# usb_hub_test.net
KiCad netlist of a schematic drawn in EAGLE
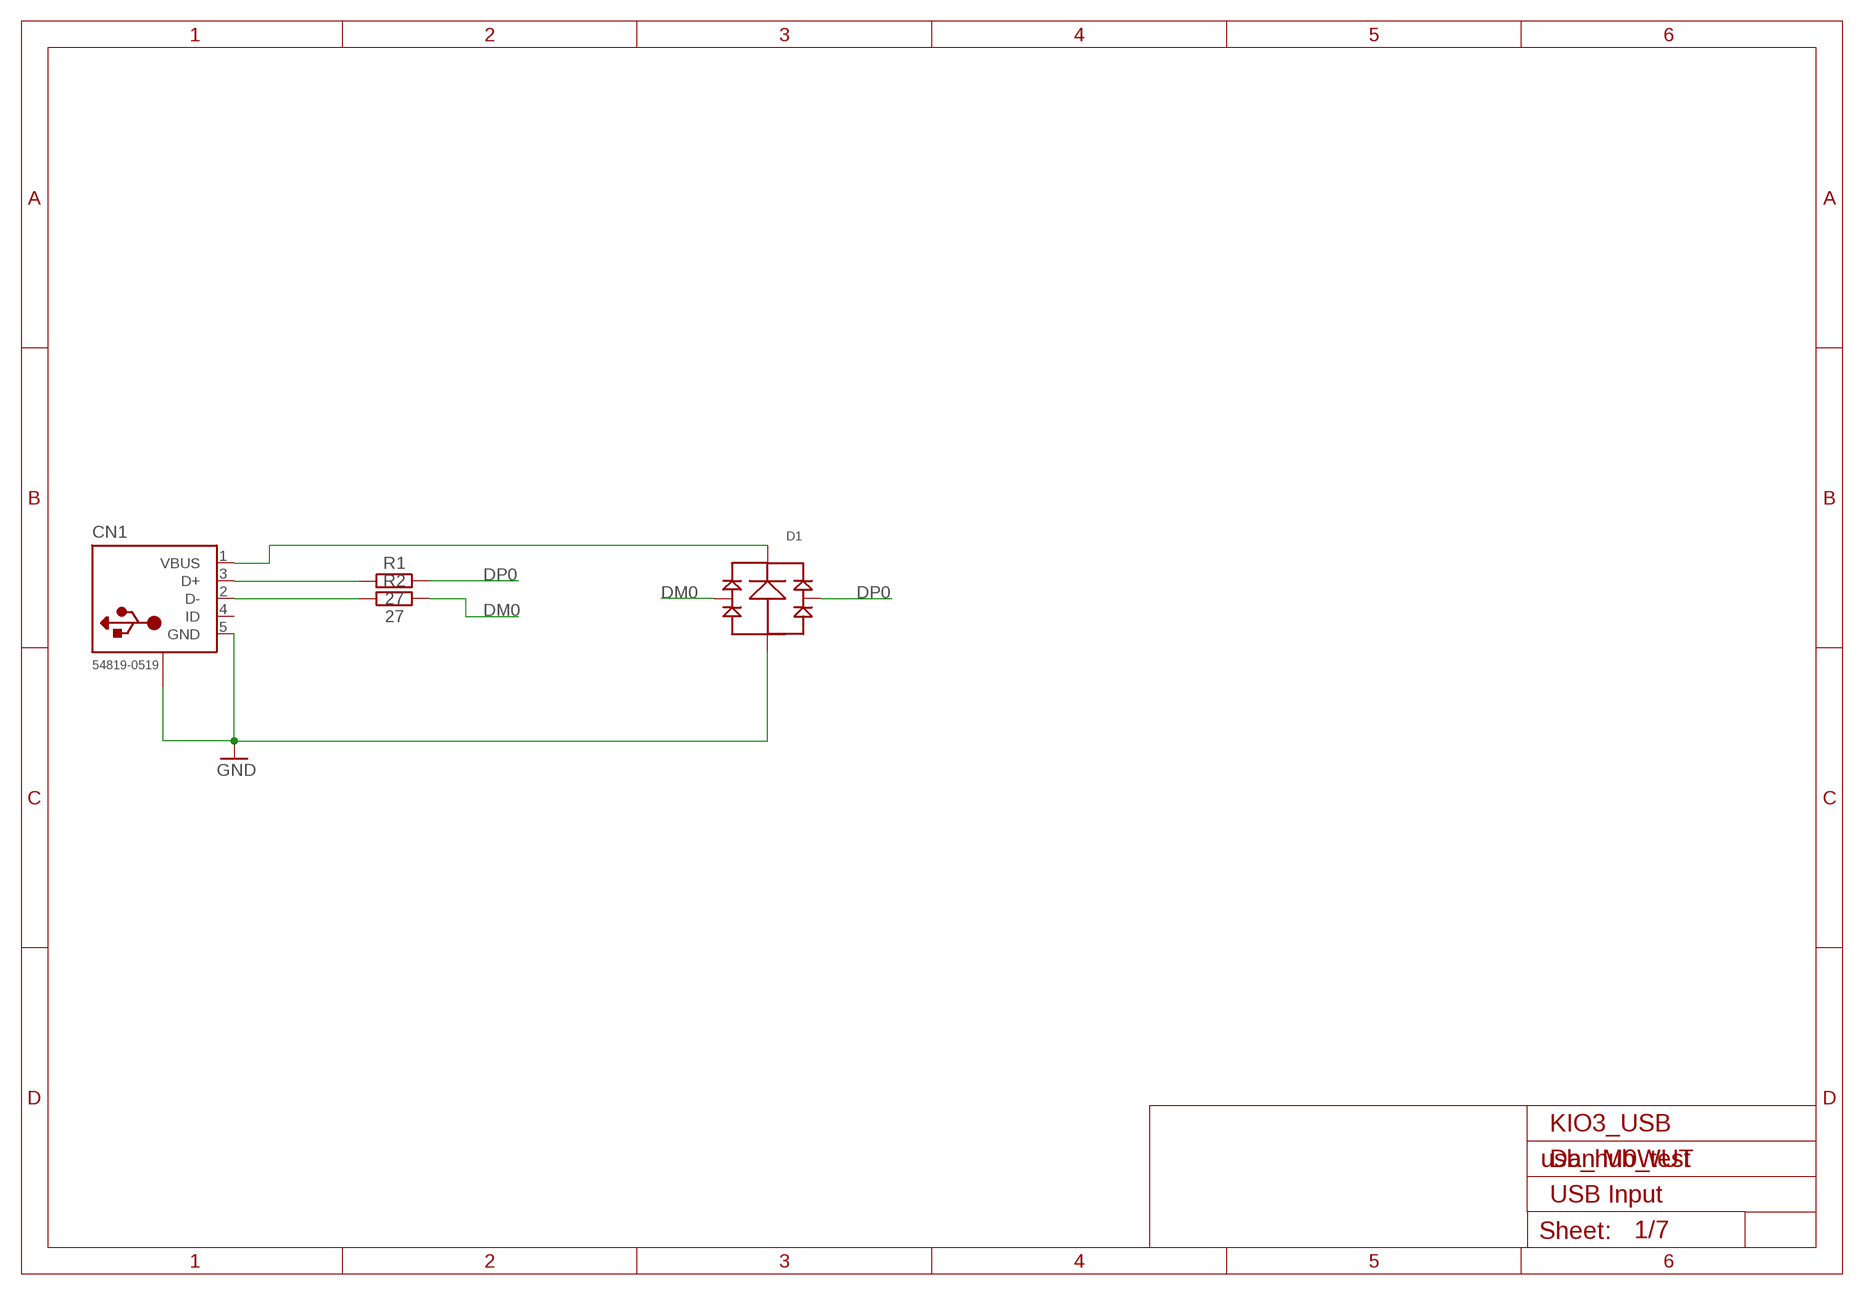
[diagram p0: schematic, sheet 1]
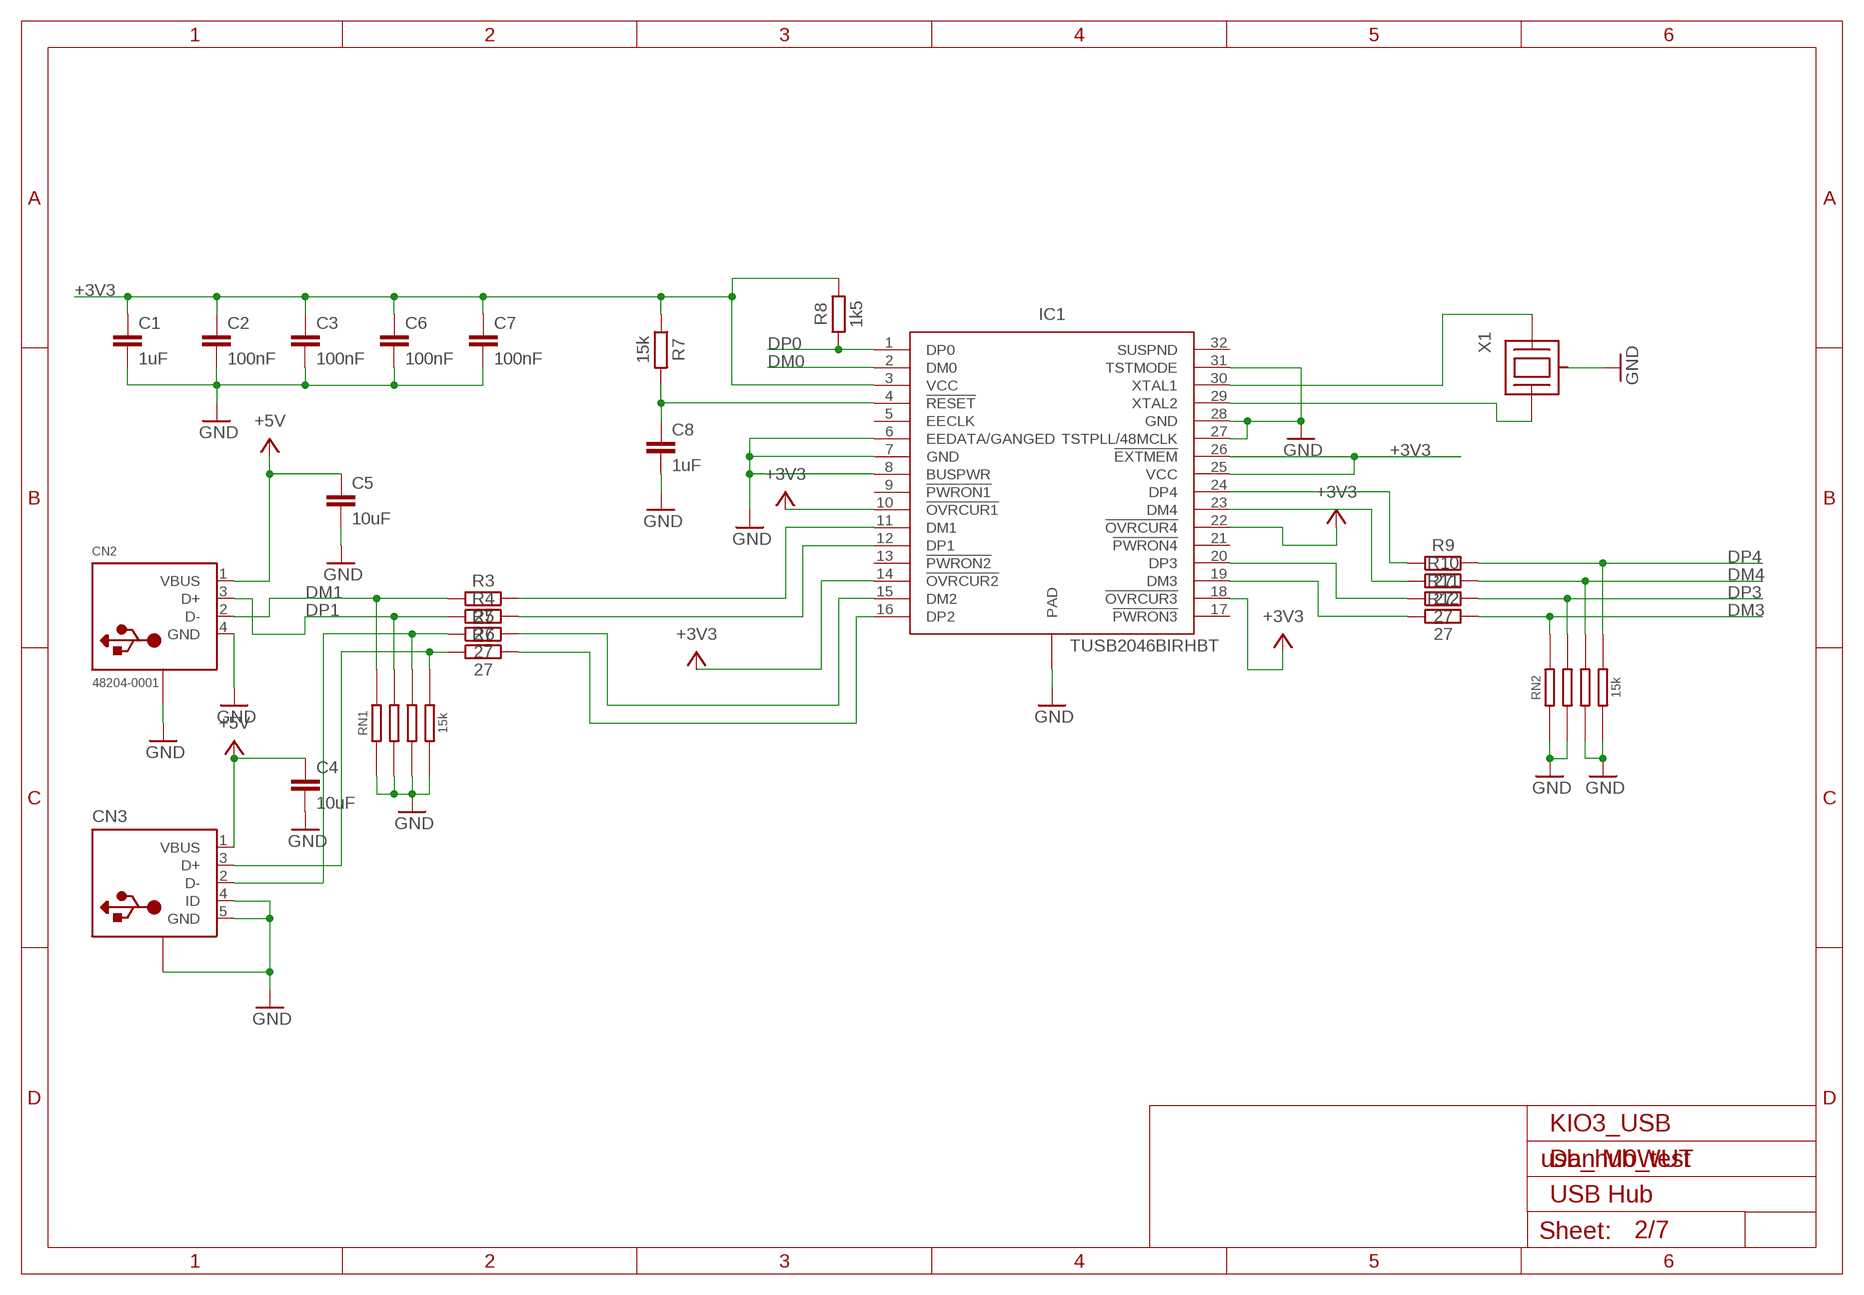
[diagram p1: schematic, sheet 2]
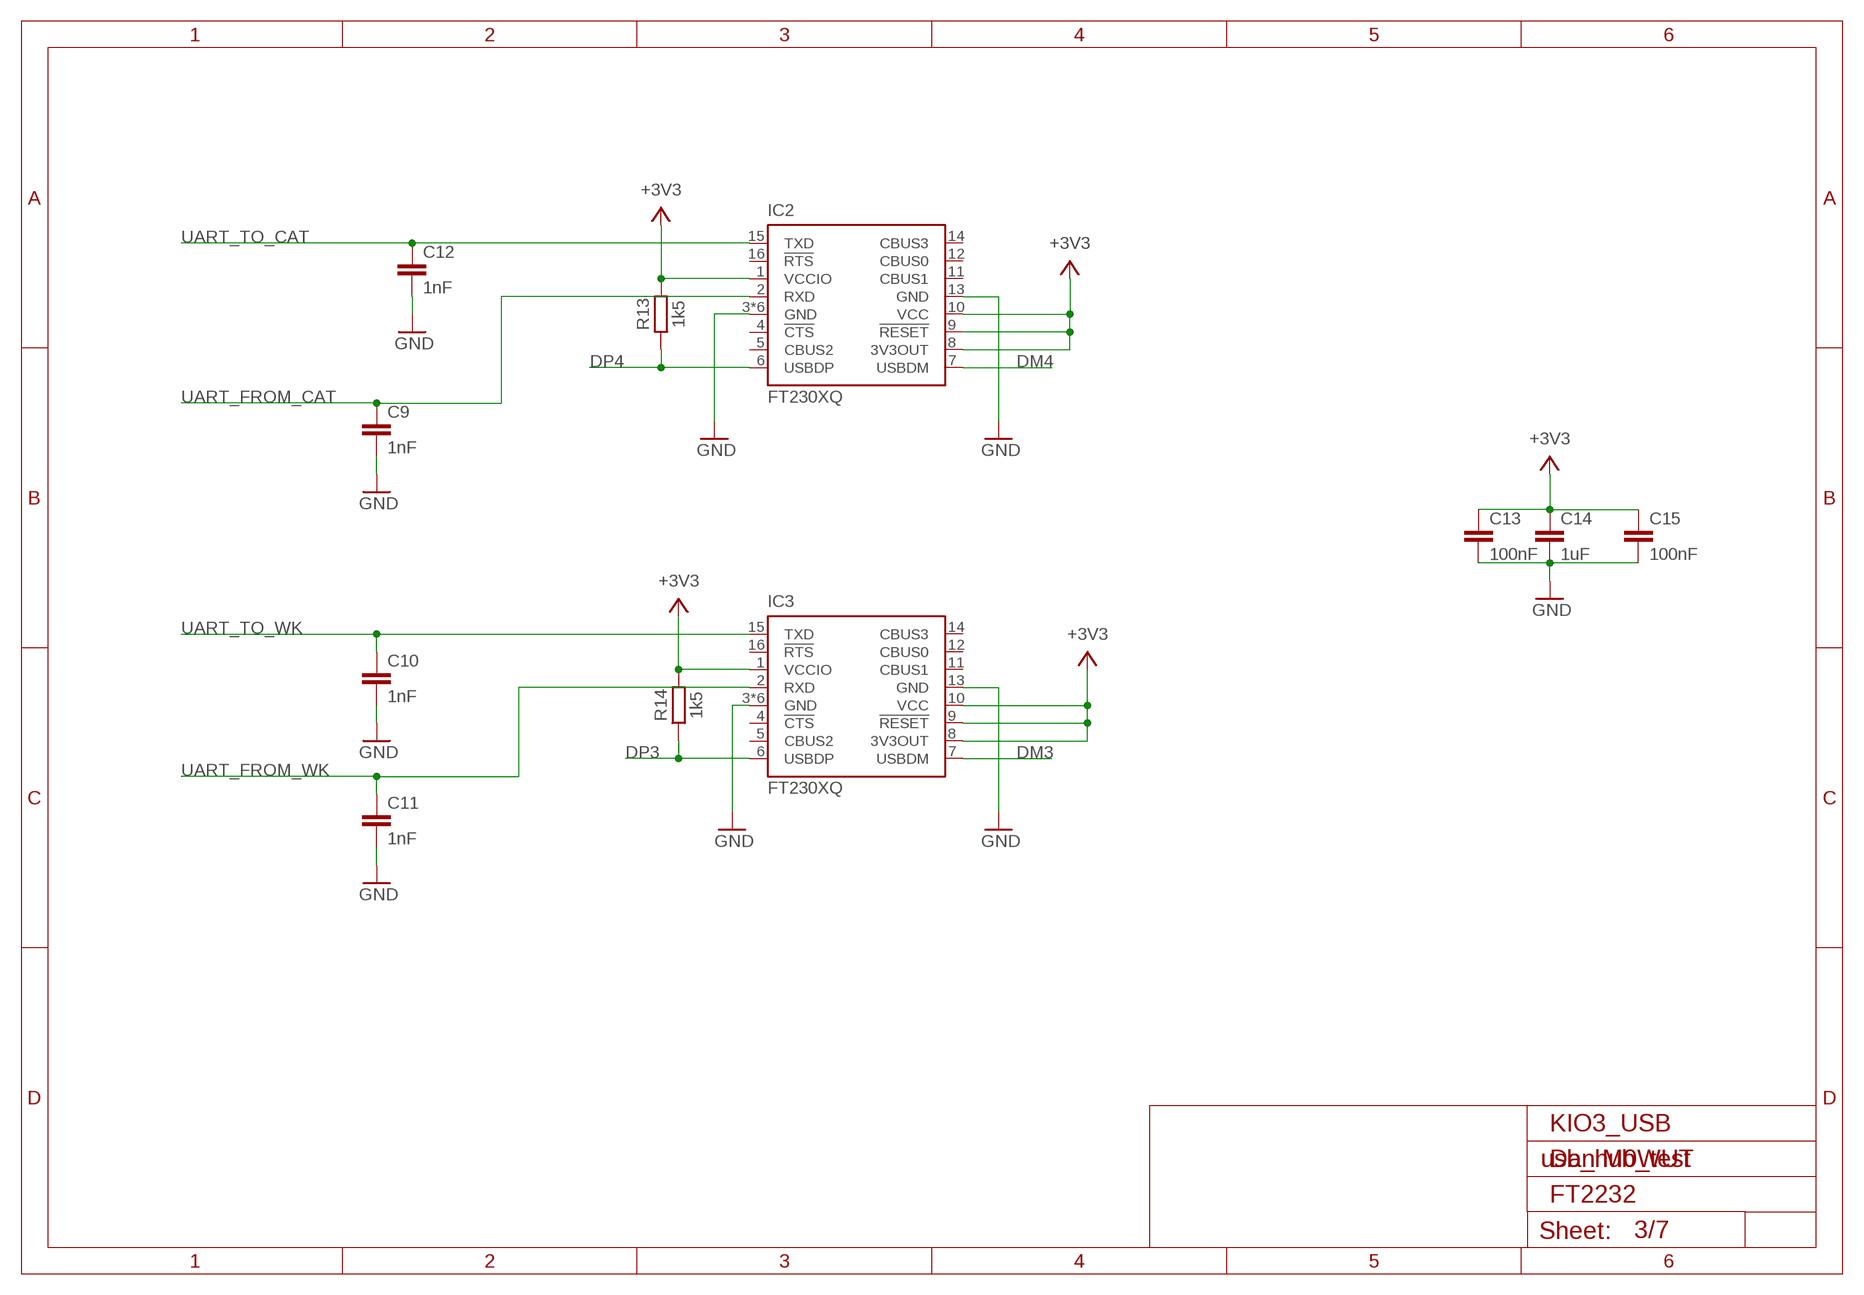
[diagram p2: schematic, sheet 3]
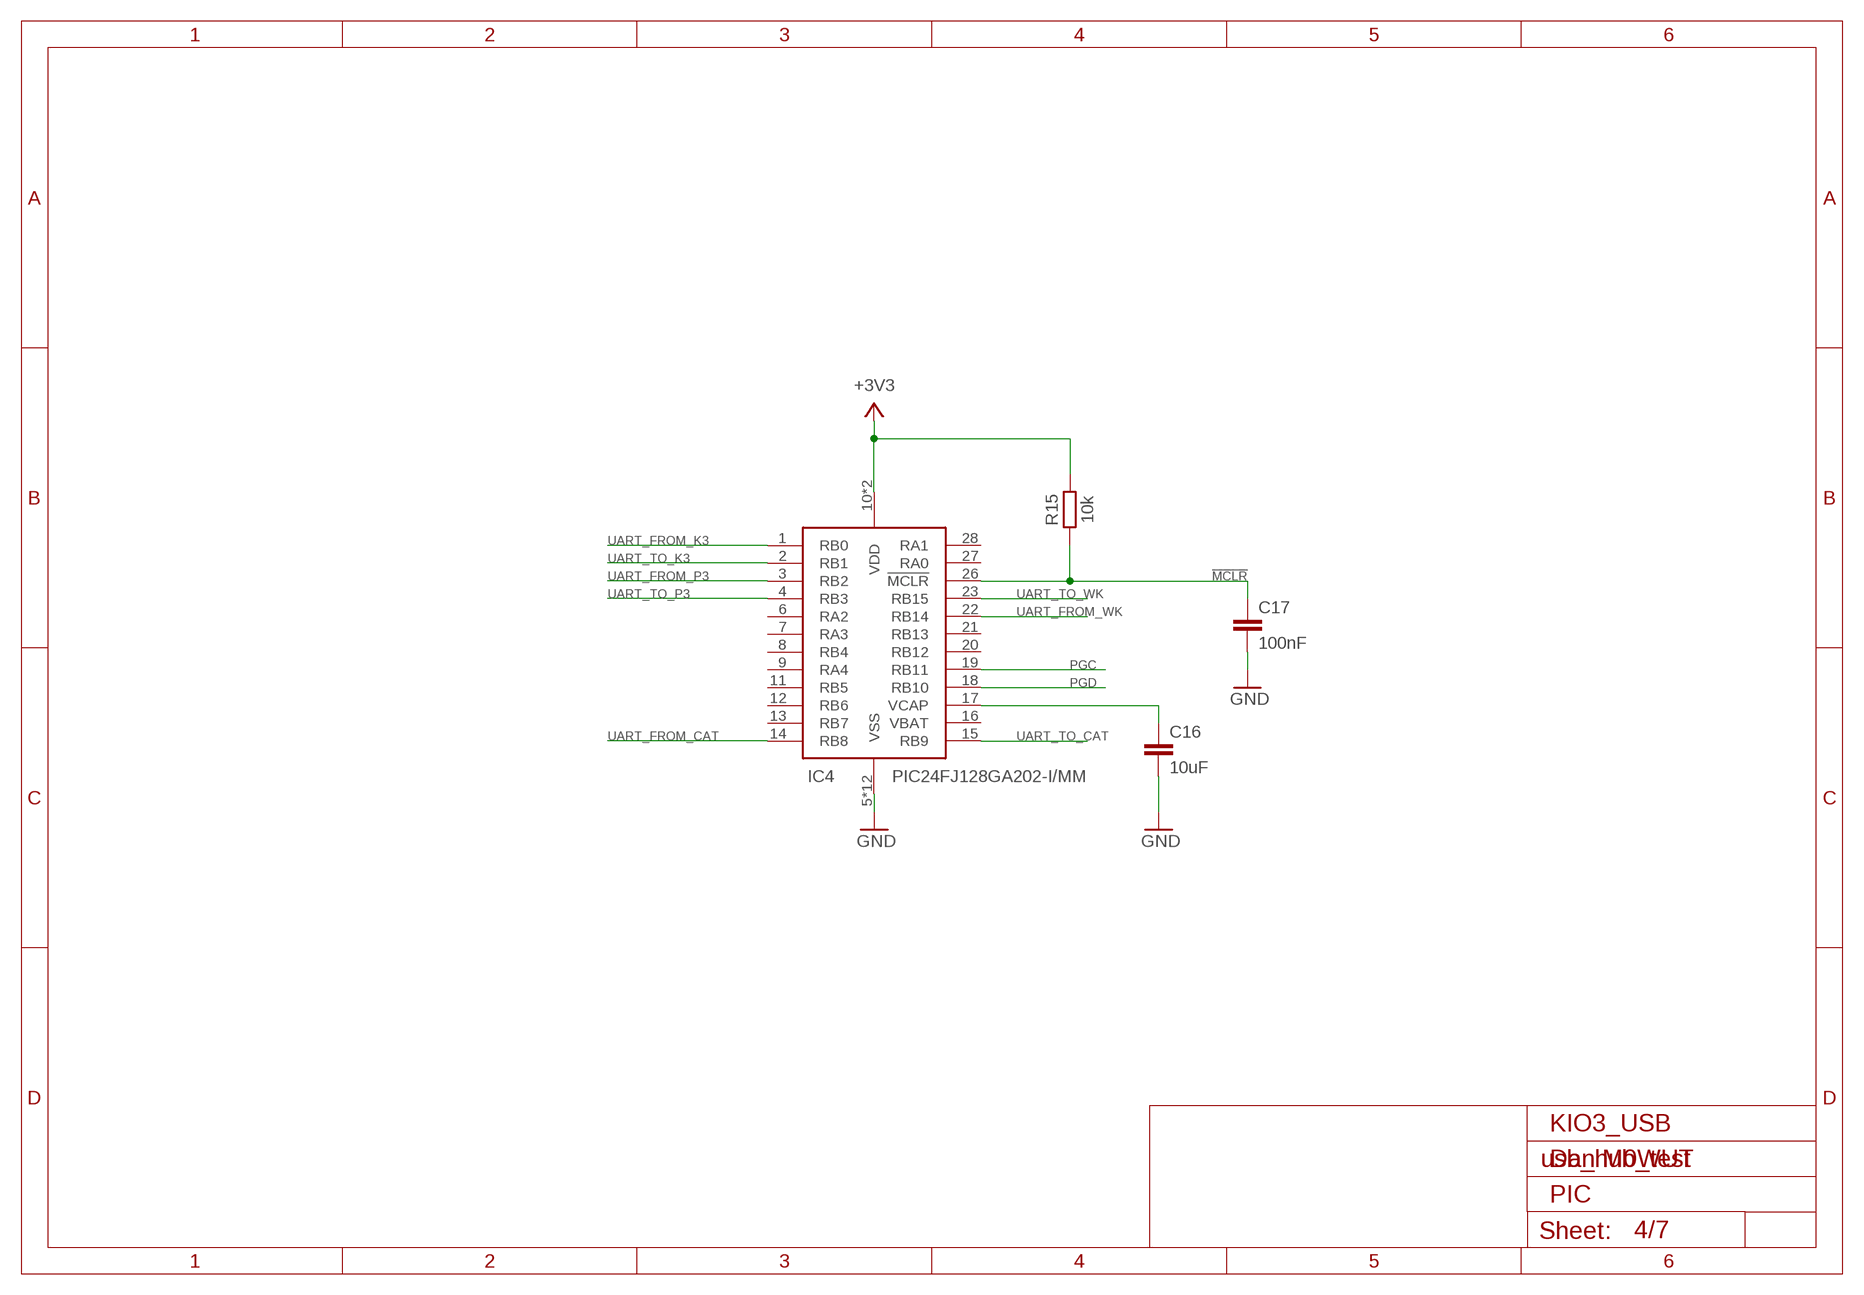
[diagram p3: schematic, sheet 4]
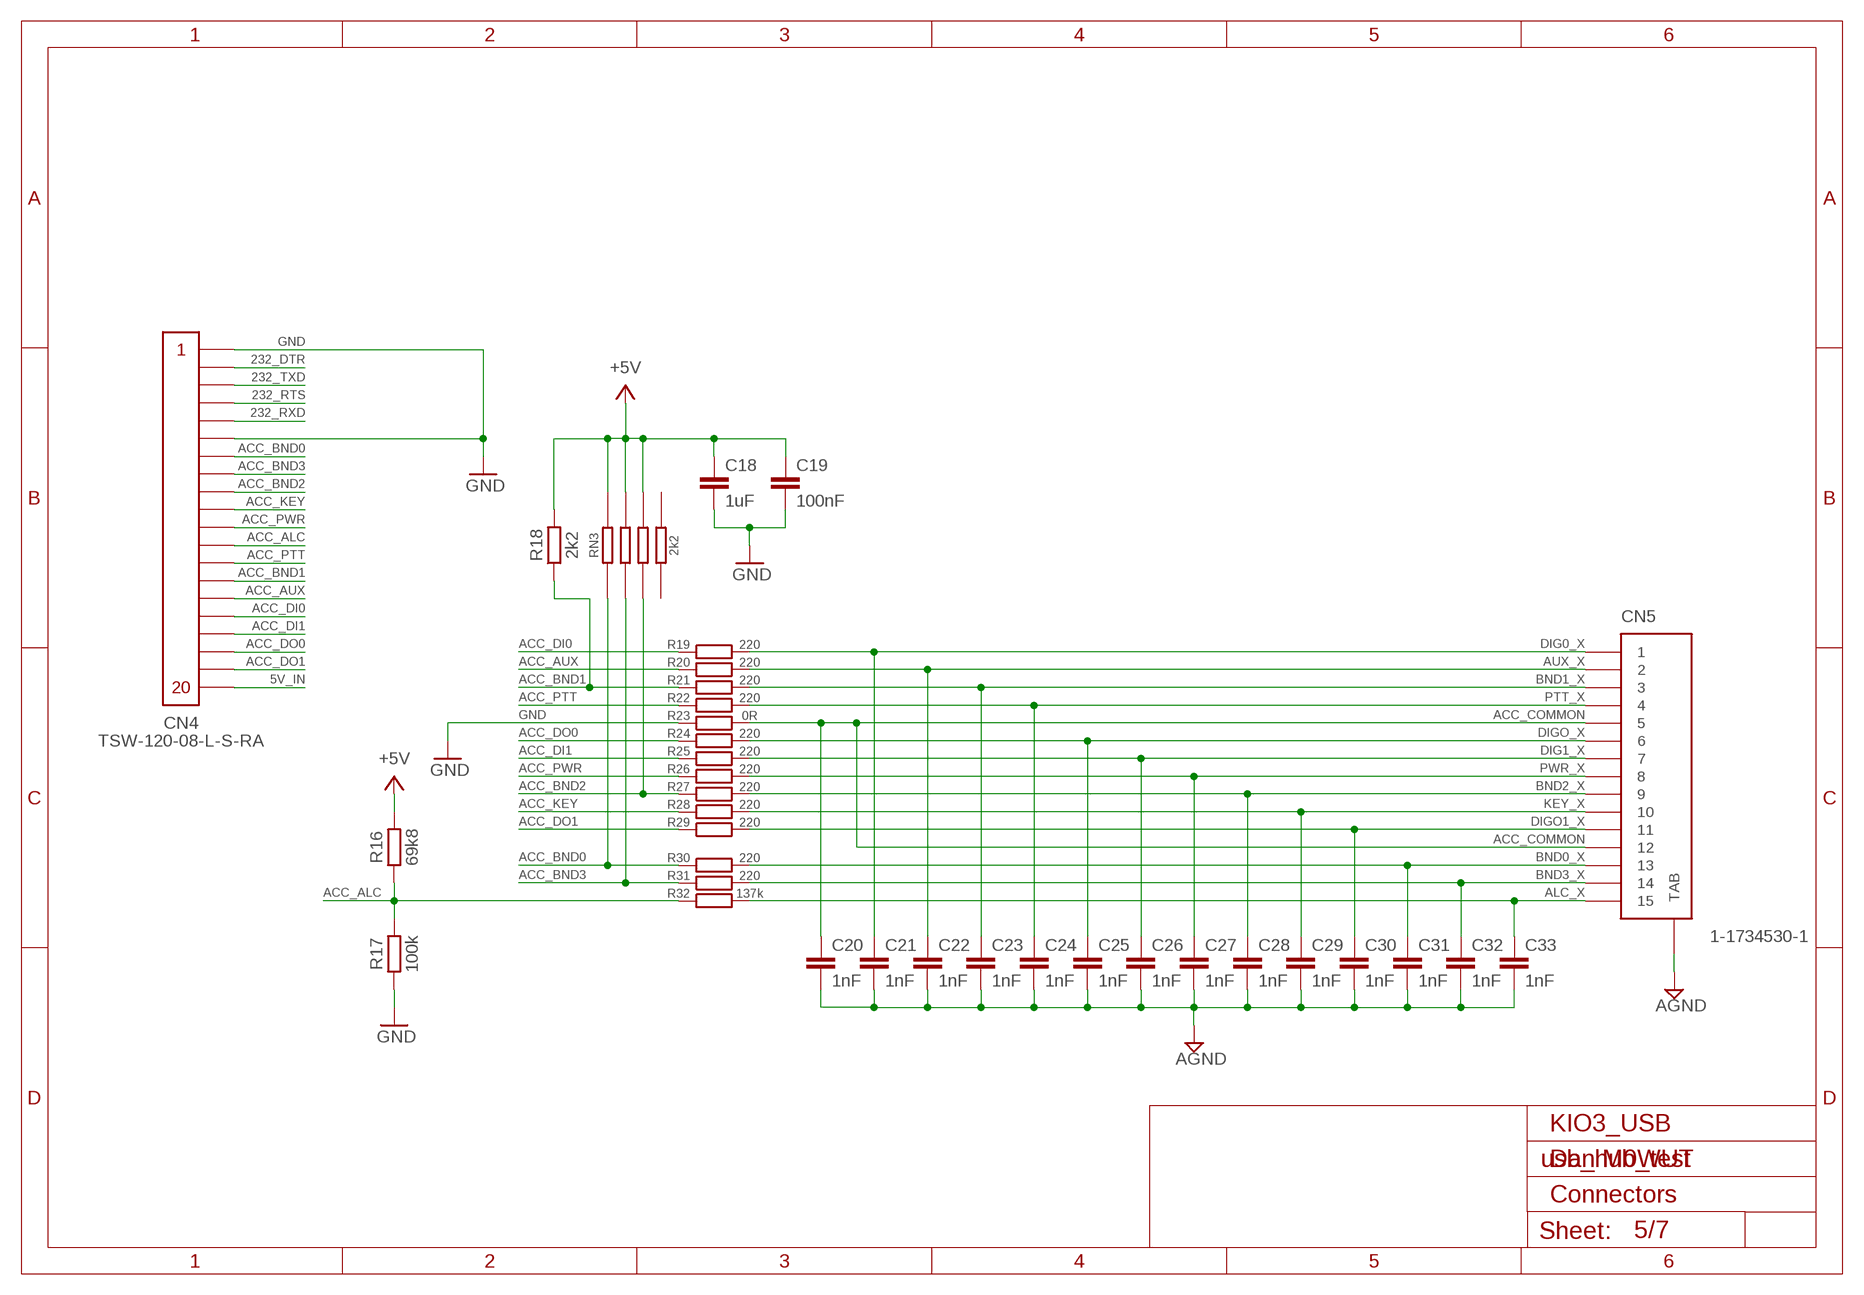
[diagram p4: schematic, sheet 5]
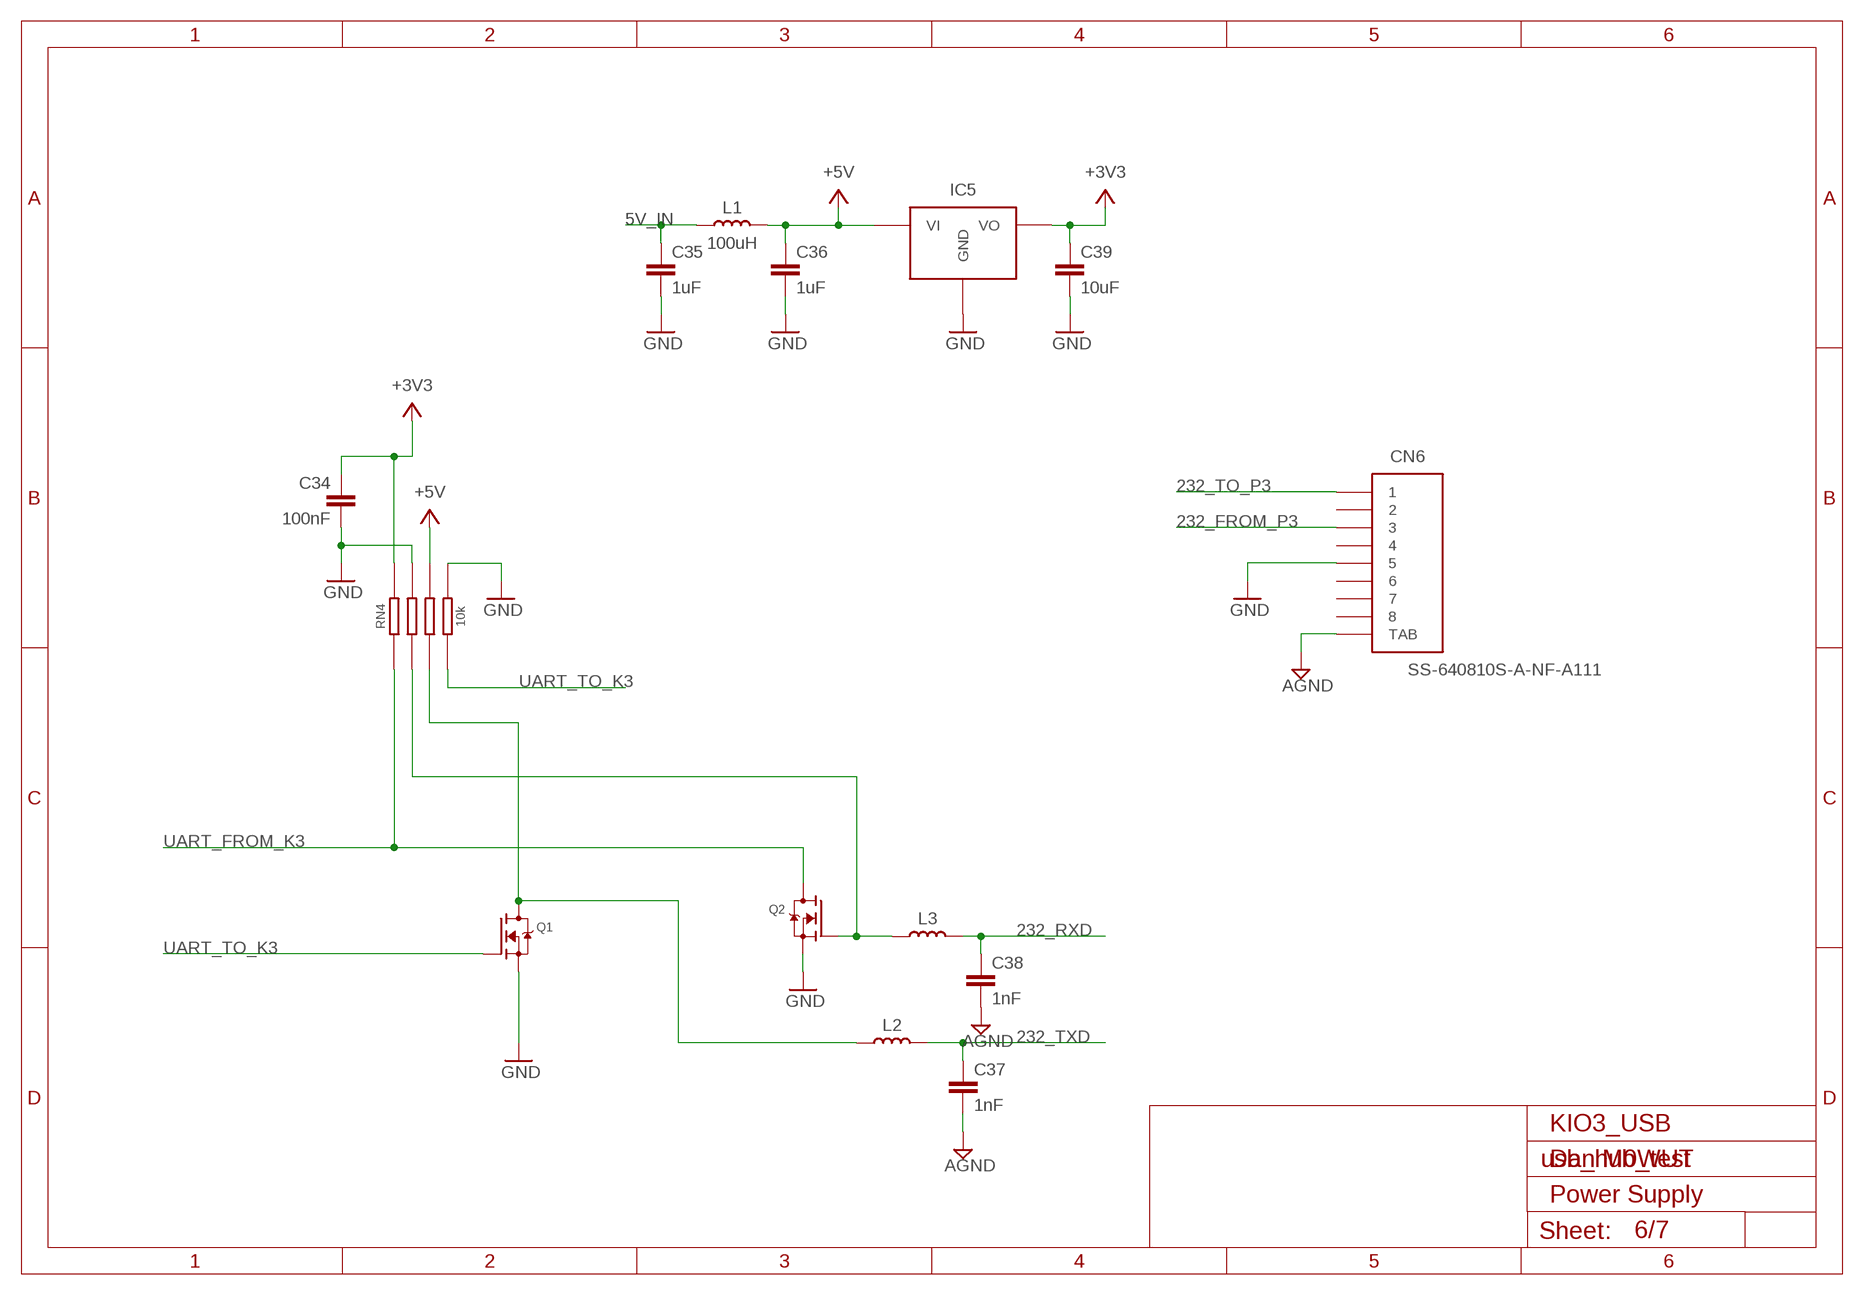
[diagram p5: schematic, sheet 6]
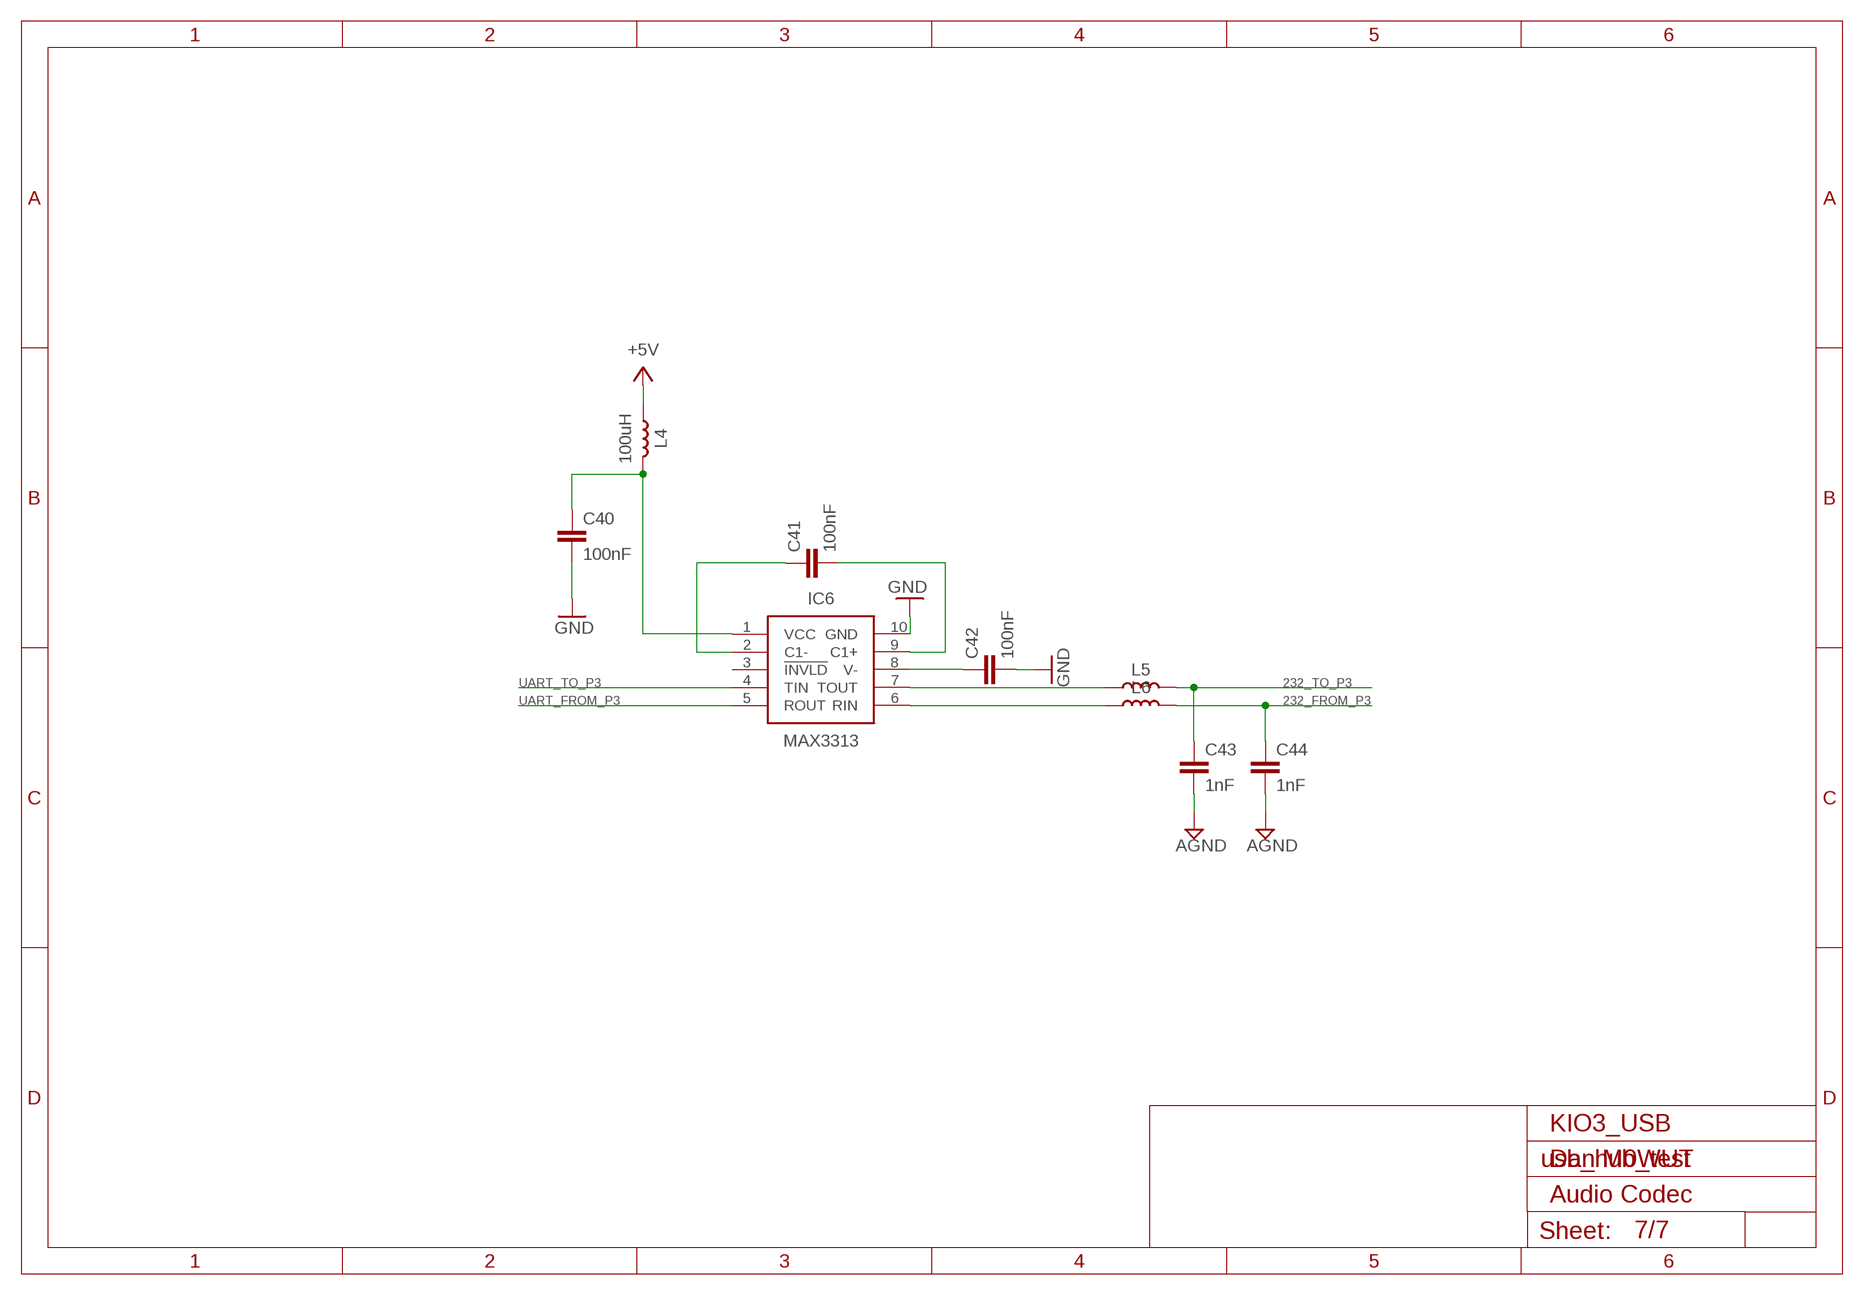
[diagram p6: schematic, sheet 7]

(export (version "E")
  (design (tool "Eeschema 10.0.6"))
  (components
    (comp (ref "C16")
      (value "10uF")
      (footprint "eagle-import:C0805")
      (libsource (lib "eagle-import") (part "C-EUC0805"))
    )
    (comp (ref "C17")
      (value "100nF")
      (footprint "eagle-import:C0402")
      (libsource (lib "eagle-import") (part "C-EUC0402"))
    )
    (comp (ref "IC4")
      (value "PIC24FJ128GA202-I/MM")
      (footprint "eagle-import:QFN28-ML_6X6MM")
      (libsource (lib "eagle-import") (part "PIC24FJ128GA202-I/MM"))
    )
    (comp (ref "R15")
      (value "10k")
      (footprint "eagle-import:R0402")
      (libsource (lib "eagle-import") (part "R-EU_R0402"))
    )
    (comp (ref "C34")
      (value "100nF")
      (footprint "eagle-import:C0402")
      (libsource (lib "eagle-import") (part "C-EUC0402"))
    )
    (comp (ref "C35")
      (value "1uF")
      (footprint "eagle-import:C0402")
      (libsource (lib "eagle-import") (part "C-EUC0402"))
    )
    (comp (ref "C36")
      (value "1uF")
      (footprint "eagle-import:C0402")
      (libsource (lib "eagle-import") (part "C-EUC0402"))
    )
    (comp (ref "C37")
      (value "1nF")
      (footprint "eagle-import:C0402")
      (libsource (lib "eagle-import") (part "C-EUC0402"))
    )
    (comp (ref "C38")
      (value "1nF")
      (footprint "eagle-import:C0402")
      (libsource (lib "eagle-import") (part "C-EUC0402"))
    )
    (comp (ref "C39")
      (value "10uF")
      (footprint "eagle-import:C0805")
      (libsource (lib "eagle-import") (part "C-EUC0805"))
    )
    (comp (ref "CN6")
      (value "SS-640810S-A-NF-A111")
      (footprint "eagle-import:CONN_STEWART_RJ45_1")
      (libsource (lib "eagle-import") (part "CONN_RJ45_SHIELDEDSTEWART_SHORTER"))
    )
    (comp (ref "IC5")
      (value "MCP1700")
      (footprint "eagle-import:SOT23")
      (libsource (lib "eagle-import") (part "MCP1700"))
    )
    (comp (ref "L1")
      (value "100uH")
      (footprint "eagle-import:R0805")
      (libsource (lib "eagle-import") (part "INDUCTOR"))
    )
    (comp (ref "L2")
      (value "INDUCTOR")
      (footprint "eagle-import:R0805")
      (libsource (lib "eagle-import") (part "INDUCTOR"))
    )
    (comp (ref "L3")
      (value "INDUCTOR")
      (footprint "eagle-import:R0805")
      (libsource (lib "eagle-import") (part "INDUCTOR"))
    )
    (comp (ref "Q1")
      (value "MOSFET-NREFLOW")
      (footprint "eagle-import:SOT23")
      (libsource (lib "eagle-import") (part "MOSFET-NREFLOW"))
    )
    (comp (ref "Q2")
      (value "MOSFET-NREFLOW")
      (footprint "eagle-import:SOT23")
      (libsource (lib "eagle-import") (part "MOSFET-NREFLOW"))
    )
    (comp (ref "RN4")
      (value "10k")
      (footprint "eagle-import:R_BOURNS_CAY16-J4")
      (libsource (lib "eagle-import") (part "R_BOURNS_CAY16-J4"))
    )
    (comp (ref "C1")
      (value "1uF")
      (footprint "eagle-import:C0402")
      (libsource (lib "eagle-import") (part "C-EUC0402"))
    )
    (comp (ref "C2")
      (value "100nF")
      (footprint "eagle-import:C0402")
      (libsource (lib "eagle-import") (part "C-EUC0402"))
    )
    (comp (ref "C3")
      (value "100nF")
      (footprint "eagle-import:C0402")
      (libsource (lib "eagle-import") (part "C-EUC0402"))
    )
    (comp (ref "C4")
      (value "10uF")
      (footprint "eagle-import:C0805")
      (libsource (lib "eagle-import") (part "C-EUC0805"))
    )
    (comp (ref "C5")
      (value "10uF")
      (footprint "eagle-import:C0805")
      (libsource (lib "eagle-import") (part "C-EUC0805"))
    )
    (comp (ref "C6")
      (value "100nF")
      (footprint "eagle-import:C0402")
      (libsource (lib "eagle-import") (part "C-EUC0402"))
    )
    (comp (ref "C7")
      (value "100nF")
      (footprint "eagle-import:C0402")
      (libsource (lib "eagle-import") (part "C-EUC0402"))
    )
    (comp (ref "C8")
      (value "1uF")
      (footprint "eagle-import:C0402")
      (libsource (lib "eagle-import") (part "C-EUC0402"))
    )
    (comp (ref "CN2")
      (value "48204-0001")
      (footprint "eagle-import:CONN_USB_MOLEX_RA")
      (libsource (lib "eagle-import") (part "USB_4WAY{dblquote}{dblquote}"))
    )
    (comp (ref "CN3")
      (value "USBWURTH")
      (footprint "eagle-import:USB_MICROB_WURTH")
      (libsource (lib "eagle-import") (part "USBWURTH"))
    )
    (comp (ref "IC1")
      (value "TUSB2046BIRHBT")
      (footprint "eagle-import:RHB_S-PQFP-N32")
      (libsource (lib "eagle-import") (part "TUSB2046BIRHBIRHB"))
    )
    (comp (ref "R3")
      (value "27")
      (footprint "eagle-import:R0402")
      (libsource (lib "eagle-import") (part "R-EU_R0402"))
    )
    (comp (ref "R4")
      (value "27")
      (footprint "eagle-import:R0402")
      (libsource (lib "eagle-import") (part "R-EU_R0402"))
    )
    (comp (ref "R5")
      (value "27")
      (footprint "eagle-import:R0402")
      (libsource (lib "eagle-import") (part "R-EU_R0402"))
    )
    (comp (ref "R6")
      (value "27")
      (footprint "eagle-import:R0402")
      (libsource (lib "eagle-import") (part "R-EU_R0402"))
    )
    (comp (ref "R7")
      (value "15k")
      (footprint "eagle-import:R0402")
      (libsource (lib "eagle-import") (part "R-EU_R0402"))
    )
    (comp (ref "R8")
      (value "1k5")
      (footprint "eagle-import:R0402")
      (libsource (lib "eagle-import") (part "R-EU_R0402"))
    )
    (comp (ref "R9")
      (value "27")
      (footprint "eagle-import:R0402")
      (libsource (lib "eagle-import") (part "R-EU_R0402"))
    )
    (comp (ref "R10")
      (value "27")
      (footprint "eagle-import:R0402")
      (libsource (lib "eagle-import") (part "R-EU_R0402"))
    )
    (comp (ref "R11")
      (value "27")
      (footprint "eagle-import:R0402")
      (libsource (lib "eagle-import") (part "R-EU_R0402"))
    )
    (comp (ref "R12")
      (value "27")
      (footprint "eagle-import:R0402")
      (libsource (lib "eagle-import") (part "R-EU_R0402"))
    )
    (comp (ref "RN1")
      (value "15k")
      (footprint "eagle-import:R_BOURNS_CAY16-J4")
      (libsource (lib "eagle-import") (part "R_BOURNS_CAY16-J4"))
    )
    (comp (ref "RN2")
      (value "15k")
      (footprint "eagle-import:R_BOURNS_CAY16-J4")
      (libsource (lib "eagle-import") (part "R_BOURNS_CAY16-J4"))
    )
    (comp (ref "X1")
      (value "XTAL_MURATA_3-PIN-RES")
      (footprint "eagle-import:XTAL_MURATA_3-PIN-RES")
      (libsource (lib "eagle-import") (part "XTAL_MURATA_3-PIN-RES"))
    )
    (comp (ref "C40")
      (value "100nF")
      (footprint "eagle-import:C0402")
      (libsource (lib "eagle-import") (part "C-EUC0402"))
    )
    (comp (ref "C41")
      (value "100nF")
      (footprint "eagle-import:C0402")
      (libsource (lib "eagle-import") (part "C-EUC0402"))
    )
    (comp (ref "C42")
      (value "100nF")
      (footprint "eagle-import:C0402")
      (libsource (lib "eagle-import") (part "C-EUC0402"))
    )
    (comp (ref "C43")
      (value "1nF")
      (footprint "eagle-import:C0402")
      (libsource (lib "eagle-import") (part "C-EUC0402"))
    )
    (comp (ref "C44")
      (value "1nF")
      (footprint "eagle-import:C0402")
      (libsource (lib "eagle-import") (part "C-EUC0402"))
    )
    (comp (ref "IC6")
      (value "IC_MAX3313")
      (footprint "eagle-import:IC_UMAX10")
      (libsource (lib "eagle-import") (part "IC_MAX3313"))
    )
    (comp (ref "L4")
      (value "100uH")
      (footprint "eagle-import:R0805")
      (libsource (lib "eagle-import") (part "INDUCTOR"))
    )
    (comp (ref "L5")
      (value "INDUCTOR")
      (footprint "eagle-import:R0805")
      (libsource (lib "eagle-import") (part "INDUCTOR"))
    )
    (comp (ref "L6")
      (value "INDUCTOR")
      (footprint "eagle-import:R0805")
      (libsource (lib "eagle-import") (part "INDUCTOR"))
    )
    (comp (ref "C18")
      (value "1uF")
      (footprint "eagle-import:C0402")
      (libsource (lib "eagle-import") (part "C-EUC0402"))
    )
    (comp (ref "C19")
      (value "100nF")
      (footprint "eagle-import:C0402")
      (libsource (lib "eagle-import") (part "C-EUC0402"))
    )
    (comp (ref "C20")
      (value "1nF")
      (footprint "eagle-import:C0402")
      (libsource (lib "eagle-import") (part "C-EUC0402"))
    )
    (comp (ref "C21")
      (value "1nF")
      (footprint "eagle-import:C0402")
      (libsource (lib "eagle-import") (part "C-EUC0402"))
    )
    (comp (ref "C22")
      (value "1nF")
      (footprint "eagle-import:C0402")
      (libsource (lib "eagle-import") (part "C-EUC0402"))
    )
    (comp (ref "C23")
      (value "1nF")
      (footprint "eagle-import:C0402")
      (libsource (lib "eagle-import") (part "C-EUC0402"))
    )
    (comp (ref "C24")
      (value "1nF")
      (footprint "eagle-import:C0402")
      (libsource (lib "eagle-import") (part "C-EUC0402"))
    )
    (comp (ref "C25")
      (value "1nF")
      (footprint "eagle-import:C0402")
      (libsource (lib "eagle-import") (part "C-EUC0402"))
    )
    (comp (ref "C26")
      (value "1nF")
      (footprint "eagle-import:C0402")
      (libsource (lib "eagle-import") (part "C-EUC0402"))
    )
    (comp (ref "C27")
      (value "1nF")
      (footprint "eagle-import:C0402")
      (libsource (lib "eagle-import") (part "C-EUC0402"))
    )
    (comp (ref "C28")
      (value "1nF")
      (footprint "eagle-import:C0402")
      (libsource (lib "eagle-import") (part "C-EUC0402"))
    )
    (comp (ref "C29")
      (value "1nF")
      (footprint "eagle-import:C0402")
      (libsource (lib "eagle-import") (part "C-EUC0402"))
    )
    (comp (ref "C30")
      (value "1nF")
      (footprint "eagle-import:C0402")
      (libsource (lib "eagle-import") (part "C-EUC0402"))
    )
    (comp (ref "C31")
      (value "1nF")
      (footprint "eagle-import:C0402")
      (libsource (lib "eagle-import") (part "C-EUC0402"))
    )
    (comp (ref "C32")
      (value "1nF")
      (footprint "eagle-import:C0402")
      (libsource (lib "eagle-import") (part "C-EUC0402"))
    )
    (comp (ref "C33")
      (value "1nF")
      (footprint "eagle-import:C0402")
      (libsource (lib "eagle-import") (part "C-EUC0402"))
    )
    (comp (ref "CN4")
      (value "TSW-120-08-L-S-RA")
      (footprint "eagle-import:CONN_0.1_1X20")
      (libsource (lib "eagle-import") (part "CONN_0.1{dblquote}_1X20"))
    )
    (comp (ref "CN5")
      (value "1-1734530-1")
      (footprint "eagle-import:CONN_TE_DE-HD15")
      (libsource (lib "eagle-import") (part "CONN_TE_DB-HD15"))
    )
    (comp (ref "R16")
      (value "69k8")
      (footprint "eagle-import:R0402")
      (libsource (lib "eagle-import") (part "R-EU_R0402"))
    )
    (comp (ref "R17")
      (value "100k")
      (footprint "eagle-import:R0402")
      (libsource (lib "eagle-import") (part "R-EU_R0402"))
    )
    (comp (ref "R18")
      (value "2k2")
      (footprint "eagle-import:R0402")
      (libsource (lib "eagle-import") (part "R-EU_R0402"))
    )
    (comp (ref "R19")
      (value "220")
      (footprint "eagle-import:R0402")
      (libsource (lib "eagle-import") (part "R-EU_R0402"))
    )
    (comp (ref "R20")
      (value "220")
      (footprint "eagle-import:R0402")
      (libsource (lib "eagle-import") (part "R-EU_R0402"))
    )
    (comp (ref "R21")
      (value "220")
      (footprint "eagle-import:R0402")
      (libsource (lib "eagle-import") (part "R-EU_R0402"))
    )
    (comp (ref "R22")
      (value "220")
      (footprint "eagle-import:R0402")
      (libsource (lib "eagle-import") (part "R-EU_R0402"))
    )
    (comp (ref "R23")
      (value "0R")
      (footprint "eagle-import:R0402")
      (libsource (lib "eagle-import") (part "R-EU_R0402"))
    )
    (comp (ref "R24")
      (value "220")
      (footprint "eagle-import:R0402")
      (libsource (lib "eagle-import") (part "R-EU_R0402"))
    )
    (comp (ref "R25")
      (value "220")
      (footprint "eagle-import:R0402")
      (libsource (lib "eagle-import") (part "R-EU_R0402"))
    )
    (comp (ref "R26")
      (value "220")
      (footprint "eagle-import:R0402")
      (libsource (lib "eagle-import") (part "R-EU_R0402"))
    )
    (comp (ref "R27")
      (value "220")
      (footprint "eagle-import:R0402")
      (libsource (lib "eagle-import") (part "R-EU_R0402"))
    )
    (comp (ref "R28")
      (value "220")
      (footprint "eagle-import:R0402")
      (libsource (lib "eagle-import") (part "R-EU_R0402"))
    )
    (comp (ref "R29")
      (value "220")
      (footprint "eagle-import:R0402")
      (libsource (lib "eagle-import") (part "R-EU_R0402"))
    )
    (comp (ref "R30")
      (value "220")
      (footprint "eagle-import:R0402")
      (libsource (lib "eagle-import") (part "R-EU_R0402"))
    )
    (comp (ref "R31")
      (value "220")
      (footprint "eagle-import:R0402")
      (libsource (lib "eagle-import") (part "R-EU_R0402"))
    )
    (comp (ref "R32")
      (value "137k")
      (footprint "eagle-import:R0402")
      (libsource (lib "eagle-import") (part "R-EU_R0402"))
    )
    (comp (ref "RN3")
      (value "2k2")
      (footprint "eagle-import:R_BOURNS_CAY16-J4")
      (libsource (lib "eagle-import") (part "R_BOURNS_CAY16-J4"))
    )
    (comp (ref "C9")
      (value "1nF")
      (footprint "eagle-import:C0402")
      (libsource (lib "eagle-import") (part "C-EUC0402"))
    )
    (comp (ref "C10")
      (value "1nF")
      (footprint "eagle-import:C0402")
      (libsource (lib "eagle-import") (part "C-EUC0402"))
    )
    (comp (ref "C11")
      (value "1nF")
      (footprint "eagle-import:C0402")
      (libsource (lib "eagle-import") (part "C-EUC0402"))
    )
    (comp (ref "C12")
      (value "1nF")
      (footprint "eagle-import:C0402")
      (libsource (lib "eagle-import") (part "C-EUC0402"))
    )
    (comp (ref "C13")
      (value "100nF")
      (footprint "eagle-import:C0402")
      (libsource (lib "eagle-import") (part "C-EUC0402"))
    )
    (comp (ref "C14")
      (value "1uF")
      (footprint "eagle-import:C0402")
      (libsource (lib "eagle-import") (part "C-EUC0402"))
    )
    (comp (ref "C15")
      (value "100nF")
      (footprint "eagle-import:C0402")
      (libsource (lib "eagle-import") (part "C-EUC0402"))
    )
    (comp (ref "IC2")
      (value "FT230XQ")
      (footprint "eagle-import:QFN16")
      (libsource (lib "eagle-import") (part "FT230XQ"))
    )
    (comp (ref "IC3")
      (value "FT230XQ")
      (footprint "eagle-import:QFN16")
      (libsource (lib "eagle-import") (part "FT230XQ"))
    )
    (comp (ref "R13")
      (value "1k5")
      (footprint "eagle-import:R0402")
      (libsource (lib "eagle-import") (part "R-EU_R0402"))
    )
    (comp (ref "R14")
      (value "1k5")
      (footprint "eagle-import:R0402")
      (libsource (lib "eagle-import") (part "R-EU_R0402"))
    )
    (comp (ref "CN1")
      (value "54819-0519")
      (footprint "eagle-import:CONN_AMP_MUSB_K152")
      (libsource (lib "eagle-import") (part "USBMUSB"))
    )
    (comp (ref "D1")
      (value "D_ST_USBULC6")
      (footprint "eagle-import:UQFN6")
      (libsource (lib "eagle-import") (part "D_ST_USBULC6"))
    )
    (comp (ref "R1")
      (value "27")
      (footprint "eagle-import:R0402")
      (libsource (lib "eagle-import") (part "R-EU_R0402"))
    )
    (comp (ref "R2")
      (value "27")
      (footprint "eagle-import:R0402")
      (libsource (lib "eagle-import") (part "R-EU_R0402"))
    )
  )
  (nets
    (net (code "1") (name "+3V3") (class "Default")
      (node (ref "C1") (pin "1") (pinfunction "1_1") (pintype "passive"))
      (node (ref "C13") (pin "1") (pinfunction "1_1") (pintype "passive"))
      (node (ref "C14") (pin "1") (pinfunction "1_1") (pintype "passive"))
      (node (ref "C15") (pin "1") (pinfunction "1_1") (pintype "passive"))
      (node (ref "C2") (pin "1") (pinfunction "1_1") (pintype "passive"))
      (node (ref "C3") (pin "1") (pinfunction "1_1") (pintype "passive"))
      (node (ref "C34") (pin "1") (pinfunction "1_1") (pintype "passive"))
      (node (ref "C39") (pin "1") (pinfunction "1_1") (pintype "passive"))
      (node (ref "C6") (pin "1") (pinfunction "1_1") (pintype "passive"))
      (node (ref "C7") (pin "1") (pinfunction "1_1") (pintype "passive"))
      (node (ref "IC1") (pin "10") (pinfunction "~{OVRCUR1}_10") (pintype "input"))
      (node (ref "IC1") (pin "14") (pinfunction "~{OVRCUR2}_14") (pintype "input"))
      (node (ref "IC1") (pin "18") (pinfunction "~{OVRCUR3}_18") (pintype "input"))
      (node (ref "IC1") (pin "22") (pinfunction "~{OVRCUR4}_22") (pintype "input"))
      (node (ref "IC1") (pin "25") (pinfunction "VCC_25") (pintype "power_in"))
      (node (ref "IC1") (pin "26") (pinfunction "~{EXTMEM}_26") (pintype "input"))
      (node (ref "IC1") (pin "3") (pinfunction "VCC_3") (pintype "power_in"))
      (node (ref "IC2") (pin "1") (pinfunction "VCCIO_1") (pintype "power_in"))
      (node (ref "IC2") (pin "10") (pinfunction "VCC_10") (pintype "power_in"))
      (node (ref "IC2") (pin "8") (pinfunction "3V3OUT_8") (pintype "output"))
      (node (ref "IC2") (pin "9") (pinfunction "~{RESET}_9") (pintype "input"))
      (node (ref "IC3") (pin "1") (pinfunction "VCCIO_1") (pintype "power_in"))
      (node (ref "IC3") (pin "10") (pinfunction "VCC_10") (pintype "power_in"))
      (node (ref "IC3") (pin "8") (pinfunction "3V3OUT_8") (pintype "output"))
      (node (ref "IC3") (pin "9") (pinfunction "~{RESET}_9") (pintype "input"))
      (node (ref "IC4") (pin "10") (pinfunction "VDD_10") (pintype "bidirectional"))
      (node (ref "IC4") (pin "25") (pinfunction "VDD_25") (pintype "bidirectional"))
      (node (ref "IC5") (pin "BOTTOM_RIGHT") (pinfunction "VO_BOTTOM_RIGHT") (pintype "bidirectional"))
      (node (ref "R13") (pin "2") (pinfunction "2_2") (pintype "passive"))
      (node (ref "R14") (pin "2") (pinfunction "2_2") (pintype "passive"))
      (node (ref "R15") (pin "2") (pinfunction "2_2") (pintype "passive"))
      (node (ref "R7") (pin "1") (pinfunction "1_1") (pintype "passive"))
      (node (ref "R8") (pin "2") (pinfunction "2_2") (pintype "passive"))
      (node (ref "RN4") (pin "1A") (pinfunction "1A_1A") (pintype "bidirectional"))
    )
    (net (code "2") (name "+5V") (class "Default")
      (node (ref "C18") (pin "1") (pinfunction "1_1") (pintype "passive"))
      (node (ref "C19") (pin "1") (pinfunction "1_1") (pintype "passive"))
      (node (ref "C36") (pin "1") (pinfunction "1_1") (pintype "passive"))
      (node (ref "C4") (pin "1") (pinfunction "1_1") (pintype "passive"))
      (node (ref "C5") (pin "1") (pinfunction "1_1") (pintype "passive"))
      (node (ref "CN2") (pin "1") (pinfunction "VBUS_1") (pintype "power_in"))
      (node (ref "CN3") (pin "1") (pinfunction "VBUS_1") (pintype "power_in"))
      (node (ref "IC5") (pin "TOP") (pinfunction "VI_TOP") (pintype "bidirectional"))
      (node (ref "L1") (pin "2") (pinfunction "2_2") (pintype "bidirectional"))
      (node (ref "L4") (pin "1") (pinfunction "1_1") (pintype "bidirectional"))
      (node (ref "R16") (pin "2") (pinfunction "2_2") (pintype "passive"))
      (node (ref "R18") (pin "2") (pinfunction "2_2") (pintype "passive"))
      (node (ref "RN3") (pin "1") (pinfunction "1_1") (pintype "bidirectional"))
      (node (ref "RN3") (pin "2") (pinfunction "2_2") (pintype "bidirectional"))
      (node (ref "RN3") (pin "3") (pinfunction "3_3") (pintype "bidirectional"))
      (node (ref "RN4") (pin "3A") (pinfunction "3A_3A") (pintype "bidirectional"))
    )
    (net (code "3") (name "5V_IN") (class "Default")
      (node (ref "C35") (pin "1") (pinfunction "1_1") (pintype "passive"))
      (node (ref "CN4") (pin "P$20") (pinfunction "P$20_P$20") (pintype "bidirectional"))
      (node (ref "L1") (pin "1") (pinfunction "1_1") (pintype "bidirectional"))
    )
    (net (code "4") (name "232_DTR") (class "Default")
      (node (ref "CN4") (pin "P$2") (pinfunction "P$2_P$2") (pintype "bidirectional"))
    )
    (net (code "5") (name "232_FROM_P3") (class "Default")
      (node (ref "C44") (pin "1") (pinfunction "1_1") (pintype "passive"))
      (node (ref "CN6") (pin "3") (pinfunction "3_3") (pintype "bidirectional"))
      (node (ref "L6") (pin "2") (pinfunction "2_2") (pintype "bidirectional"))
    )
    (net (code "6") (name "232_RTS") (class "Default")
      (node (ref "CN4") (pin "P$4") (pinfunction "P$4_P$4") (pintype "bidirectional"))
    )
    (net (code "7") (name "232_RXD") (class "Default")
      (node (ref "C38") (pin "1") (pinfunction "1_1") (pintype "passive"))
      (node (ref "CN4") (pin "P$5") (pinfunction "P$5_P$5") (pintype "bidirectional"))
      (node (ref "L3") (pin "2") (pinfunction "2_2") (pintype "bidirectional"))
    )
    (net (code "8") (name "232_TO_P3") (class "Default")
      (node (ref "C43") (pin "1") (pinfunction "1_1") (pintype "passive"))
      (node (ref "CN6") (pin "1") (pinfunction "1_1") (pintype "bidirectional"))
      (node (ref "L5") (pin "2") (pinfunction "2_2") (pintype "bidirectional"))
    )
    (net (code "9") (name "232_TXD") (class "Default")
      (node (ref "C37") (pin "1") (pinfunction "1_1") (pintype "passive"))
      (node (ref "CN4") (pin "P$3") (pinfunction "P$3_P$3") (pintype "bidirectional"))
      (node (ref "L2") (pin "2") (pinfunction "2_2") (pintype "bidirectional"))
    )
    (net (code "10") (name "ACC_ALC") (class "Default")
      (node (ref "CN4") (pin "P$12") (pinfunction "P$12_P$12") (pintype "bidirectional"))
      (node (ref "R16") (pin "1") (pinfunction "1_1") (pintype "passive"))
      (node (ref "R17") (pin "2") (pinfunction "2_2") (pintype "passive"))
      (node (ref "R32") (pin "1") (pinfunction "1_1") (pintype "passive"))
    )
    (net (code "11") (name "ACC_AUX") (class "Default")
      (node (ref "CN4") (pin "P$15") (pinfunction "P$15_P$15") (pintype "bidirectional"))
      (node (ref "R20") (pin "1") (pinfunction "1_1") (pintype "passive"))
    )
    (net (code "12") (name "ACC_BND0") (class "Default")
      (node (ref "CN4") (pin "P$7") (pinfunction "P$7_P$7") (pintype "bidirectional"))
      (node (ref "R30") (pin "1") (pinfunction "1_1") (pintype "passive"))
      (node (ref "RN3") (pin "1A") (pinfunction "1A_1A") (pintype "bidirectional"))
    )
    (net (code "13") (name "ACC_BND1") (class "Default")
      (node (ref "CN4") (pin "P$14") (pinfunction "P$14_P$14") (pintype "bidirectional"))
      (node (ref "R18") (pin "1") (pinfunction "1_1") (pintype "passive"))
      (node (ref "R21") (pin "1") (pinfunction "1_1") (pintype "passive"))
    )
    (net (code "14") (name "ACC_BND2") (class "Default")
      (node (ref "CN4") (pin "P$9") (pinfunction "P$9_P$9") (pintype "bidirectional"))
      (node (ref "R27") (pin "1") (pinfunction "1_1") (pintype "passive"))
      (node (ref "RN3") (pin "3A") (pinfunction "3A_3A") (pintype "bidirectional"))
    )
    (net (code "15") (name "ACC_BND3") (class "Default")
      (node (ref "CN4") (pin "P$8") (pinfunction "P$8_P$8") (pintype "bidirectional"))
      (node (ref "R31") (pin "1") (pinfunction "1_1") (pintype "passive"))
      (node (ref "RN3") (pin "2A") (pinfunction "2A_2A") (pintype "bidirectional"))
    )
    (net (code "16") (name "ACC_COMMON") (class "Default")
      (node (ref "C20") (pin "1") (pinfunction "1_1") (pintype "passive"))
      (node (ref "CN5") (pin "12") (pinfunction "12_12") (pintype "bidirectional"))
      (node (ref "CN5") (pin "5") (pinfunction "5_5") (pintype "bidirectional"))
      (node (ref "R23") (pin "2") (pinfunction "2_2") (pintype "passive"))
    )
    (net (code "17") (name "ACC_DI0") (class "Default")
      (node (ref "CN4") (pin "P$16") (pinfunction "P$16_P$16") (pintype "bidirectional"))
      (node (ref "R19") (pin "1") (pinfunction "1_1") (pintype "passive"))
    )
    (net (code "18") (name "ACC_DI1") (class "Default")
      (node (ref "CN4") (pin "P$17") (pinfunction "P$17_P$17") (pintype "bidirectional"))
      (node (ref "R25") (pin "1") (pinfunction "1_1") (pintype "passive"))
    )
    (net (code "19") (name "ACC_DO0") (class "Default")
      (node (ref "CN4") (pin "P$18") (pinfunction "P$18_P$18") (pintype "bidirectional"))
      (node (ref "R24") (pin "1") (pinfunction "1_1") (pintype "passive"))
    )
    (net (code "20") (name "ACC_DO1") (class "Default")
      (node (ref "CN4") (pin "P$19") (pinfunction "P$19_P$19") (pintype "bidirectional"))
      (node (ref "R29") (pin "1") (pinfunction "1_1") (pintype "passive"))
    )
    (net (code "21") (name "ACC_KEY") (class "Default")
      (node (ref "CN4") (pin "P$10") (pinfunction "P$10_P$10") (pintype "bidirectional"))
      (node (ref "R28") (pin "1") (pinfunction "1_1") (pintype "passive"))
    )
    (net (code "22") (name "ACC_PTT") (class "Default")
      (node (ref "CN4") (pin "P$13") (pinfunction "P$13_P$13") (pintype "bidirectional"))
      (node (ref "R22") (pin "1") (pinfunction "1_1") (pintype "passive"))
    )
    (net (code "23") (name "ACC_PWR") (class "Default")
      (node (ref "CN4") (pin "P$11") (pinfunction "P$11_P$11") (pintype "bidirectional"))
      (node (ref "R26") (pin "1") (pinfunction "1_1") (pintype "passive"))
    )
    (net (code "24") (name "AGND") (class "Default")
      (node (ref "C20") (pin "2") (pinfunction "2_2") (pintype "passive"))
      (node (ref "C21") (pin "2") (pinfunction "2_2") (pintype "passive"))
      (node (ref "C22") (pin "2") (pinfunction "2_2") (pintype "passive"))
      (node (ref "C23") (pin "2") (pinfunction "2_2") (pintype "passive"))
      (node (ref "C24") (pin "2") (pinfunction "2_2") (pintype "passive"))
      (node (ref "C25") (pin "2") (pinfunction "2_2") (pintype "passive"))
      (node (ref "C26") (pin "2") (pinfunction "2_2") (pintype "passive"))
      (node (ref "C27") (pin "2") (pinfunction "2_2") (pintype "passive"))
      (node (ref "C28") (pin "2") (pinfunction "2_2") (pintype "passive"))
      (node (ref "C29") (pin "2") (pinfunction "2_2") (pintype "passive"))
      (node (ref "C30") (pin "2") (pinfunction "2_2") (pintype "passive"))
      (node (ref "C31") (pin "2") (pinfunction "2_2") (pintype "passive"))
      (node (ref "C32") (pin "2") (pinfunction "2_2") (pintype "passive"))
      (node (ref "C33") (pin "2") (pinfunction "2_2") (pintype "passive"))
      (node (ref "C37") (pin "2") (pinfunction "2_2") (pintype "passive"))
      (node (ref "C38") (pin "2") (pinfunction "2_2") (pintype "passive"))
      (node (ref "C43") (pin "2") (pinfunction "2_2") (pintype "passive"))
      (node (ref "C44") (pin "2") (pinfunction "2_2") (pintype "passive"))
      (node (ref "CN5") (pin "16") (pinfunction "TAB_16") (pintype "bidirectional"))
      (node (ref "CN5") (pin "17") (pinfunction "TAB_17") (pintype "bidirectional"))
      (node (ref "CN6") (pin "TAB") (pinfunction "TAB_TAB") (pintype "bidirectional"))
      (node (ref "CN6") (pin "TAB1") (pinfunction "TAB_TAB1") (pintype "bidirectional"))
    )
    (net (code "25") (name "ALC_X") (class "Default")
      (node (ref "C33") (pin "1") (pinfunction "1_1") (pintype "passive"))
      (node (ref "CN5") (pin "15") (pinfunction "15_15") (pintype "bidirectional"))
      (node (ref "R32") (pin "2") (pinfunction "2_2") (pintype "passive"))
    )
    (net (code "26") (name "AUX_X") (class "Default")
      (node (ref "C22") (pin "1") (pinfunction "1_1") (pintype "passive"))
      (node (ref "CN5") (pin "2") (pinfunction "2_2") (pintype "bidirectional"))
      (node (ref "R20") (pin "2") (pinfunction "2_2") (pintype "passive"))
    )
    (net (code "27") (name "BND0_X") (class "Default")
      (node (ref "C31") (pin "1") (pinfunction "1_1") (pintype "passive"))
      (node (ref "CN5") (pin "13") (pinfunction "13_13") (pintype "bidirectional"))
      (node (ref "R30") (pin "2") (pinfunction "2_2") (pintype "passive"))
    )
    (net (code "28") (name "BND1_X") (class "Default")
      (node (ref "C23") (pin "1") (pinfunction "1_1") (pintype "passive"))
      (node (ref "CN5") (pin "3") (pinfunction "3_3") (pintype "bidirectional"))
      (node (ref "R21") (pin "2") (pinfunction "2_2") (pintype "passive"))
    )
    (net (code "29") (name "BND2_X") (class "Default")
      (node (ref "C28") (pin "1") (pinfunction "1_1") (pintype "passive"))
      (node (ref "CN5") (pin "9") (pinfunction "9_9") (pintype "bidirectional"))
      (node (ref "R27") (pin "2") (pinfunction "2_2") (pintype "passive"))
    )
    (net (code "30") (name "BND3_X") (class "Default")
      (node (ref "C32") (pin "1") (pinfunction "1_1") (pintype "passive"))
      (node (ref "CN5") (pin "14") (pinfunction "14_14") (pintype "bidirectional"))
      (node (ref "R31") (pin "2") (pinfunction "2_2") (pintype "passive"))
    )
    (net (code "31") (name "DIG0_X") (class "Default")
      (node (ref "C21") (pin "1") (pinfunction "1_1") (pintype "passive"))
      (node (ref "CN5") (pin "1") (pinfunction "1_1") (pintype "bidirectional"))
      (node (ref "R19") (pin "2") (pinfunction "2_2") (pintype "passive"))
    )
    (net (code "32") (name "DIG1_X") (class "Default")
      (node (ref "C26") (pin "1") (pinfunction "1_1") (pintype "passive"))
      (node (ref "CN5") (pin "7") (pinfunction "7_7") (pintype "bidirectional"))
      (node (ref "R25") (pin "2") (pinfunction "2_2") (pintype "passive"))
    )
    (net (code "33") (name "DIGO1_X") (class "Default")
      (node (ref "C30") (pin "1") (pinfunction "1_1") (pintype "passive"))
      (node (ref "CN5") (pin "11") (pinfunction "11_11") (pintype "bidirectional"))
      (node (ref "R29") (pin "2") (pinfunction "2_2") (pintype "passive"))
    )
    (net (code "34") (name "DIGO_X") (class "Default")
      (node (ref "C25") (pin "1") (pinfunction "1_1") (pintype "passive"))
      (node (ref "CN5") (pin "6") (pinfunction "6_6") (pintype "bidirectional"))
      (node (ref "R24") (pin "2") (pinfunction "2_2") (pintype "passive"))
    )
    (net (code "35") (name "DM0") (class "Default")
      (node (ref "D1") (pin "1") (pinfunction "LEFT_1") (pintype "bidirectional"))
      (node (ref "D1") (pin "6") (pinfunction "LEFT_6") (pintype "bidirectional"))
      (node (ref "IC1") (pin "2") (pinfunction "DM0_2") (pintype "bidirectional"))
      (node (ref "R2") (pin "2") (pinfunction "2_2") (pintype "passive"))
    )
    (net (code "36") (name "DM1") (class "Default")
      (node (ref "CN2") (pin "2") (pinfunction "D-_2") (pintype "bidirectional"))
      (node (ref "R3") (pin "1") (pinfunction "1_1") (pintype "passive"))
      (node (ref "RN1") (pin "1A") (pinfunction "1A_1A") (pintype "bidirectional"))
    )
    (net (code "37") (name "DM3") (class "Default")
      (node (ref "IC3") (pin "7") (pinfunction "USBDM_7") (pintype "input"))
      (node (ref "R12") (pin "2") (pinfunction "2_2") (pintype "passive"))
      (node (ref "RN2") (pin "1A") (pinfunction "1A_1A") (pintype "bidirectional"))
    )
    (net (code "38") (name "DM4") (class "Default")
      (node (ref "IC2") (pin "7") (pinfunction "USBDM_7") (pintype "input"))
      (node (ref "R10") (pin "2") (pinfunction "2_2") (pintype "passive"))
      (node (ref "RN2") (pin "3A") (pinfunction "3A_3A") (pintype "bidirectional"))
    )
    (net (code "39") (name "DP0") (class "Default")
      (node (ref "D1") (pin "3") (pinfunction "RIGHT_3") (pintype "bidirectional"))
      (node (ref "D1") (pin "4") (pinfunction "RIGHT_4") (pintype "bidirectional"))
      (node (ref "IC1") (pin "1") (pinfunction "DP0_1") (pintype "bidirectional"))
      (node (ref "R1") (pin "2") (pinfunction "2_2") (pintype "passive"))
      (node (ref "R8") (pin "1") (pinfunction "1_1") (pintype "passive"))
    )
    (net (code "40") (name "DP1") (class "Default")
      (node (ref "CN2") (pin "3") (pinfunction "D+_3") (pintype "bidirectional"))
      (node (ref "R4") (pin "1") (pinfunction "1_1") (pintype "passive"))
      (node (ref "RN1") (pin "2A") (pinfunction "2A_2A") (pintype "bidirectional"))
    )
    (net (code "41") (name "DP3") (class "Default")
      (node (ref "IC3") (pin "6") (pinfunction "USBDP_6") (pintype "input"))
      (node (ref "R11") (pin "2") (pinfunction "2_2") (pintype "passive"))
      (node (ref "R14") (pin "1") (pinfunction "1_1") (pintype "passive"))
      (node (ref "RN2") (pin "2A") (pinfunction "2A_2A") (pintype "bidirectional"))
    )
    (net (code "42") (name "DP4") (class "Default")
      (node (ref "IC2") (pin "6") (pinfunction "USBDP_6") (pintype "input"))
      (node (ref "R13") (pin "1") (pinfunction "1_1") (pintype "passive"))
      (node (ref "R9") (pin "2") (pinfunction "2_2") (pintype "passive"))
      (node (ref "RN2") (pin "4A") (pinfunction "4A_4A") (pintype "bidirectional"))
    )
    (net (code "43") (name "GND") (class "Default")
      (node (ref "C1") (pin "2") (pinfunction "2_2") (pintype "passive"))
      (node (ref "C10") (pin "2") (pinfunction "2_2") (pintype "passive"))
      (node (ref "C11") (pin "2") (pinfunction "2_2") (pintype "passive"))
      (node (ref "C12") (pin "2") (pinfunction "2_2") (pintype "passive"))
      (node (ref "C13") (pin "2") (pinfunction "2_2") (pintype "passive"))
      (node (ref "C14") (pin "2") (pinfunction "2_2") (pintype "passive"))
      (node (ref "C15") (pin "2") (pinfunction "2_2") (pintype "passive"))
      (node (ref "C16") (pin "2") (pinfunction "2_2") (pintype "passive"))
      (node (ref "C17") (pin "2") (pinfunction "2_2") (pintype "passive"))
      (node (ref "C18") (pin "2") (pinfunction "2_2") (pintype "passive"))
      (node (ref "C19") (pin "2") (pinfunction "2_2") (pintype "passive"))
      (node (ref "C2") (pin "2") (pinfunction "2_2") (pintype "passive"))
      (node (ref "C3") (pin "2") (pinfunction "2_2") (pintype "passive"))
      (node (ref "C34") (pin "2") (pinfunction "2_2") (pintype "passive"))
      (node (ref "C35") (pin "2") (pinfunction "2_2") (pintype "passive"))
      (node (ref "C36") (pin "2") (pinfunction "2_2") (pintype "passive"))
      (node (ref "C39") (pin "2") (pinfunction "2_2") (pintype "passive"))
      (node (ref "C4") (pin "2") (pinfunction "2_2") (pintype "passive"))
      (node (ref "C40") (pin "2") (pinfunction "2_2") (pintype "passive"))
      (node (ref "C42") (pin "2") (pinfunction "2_2") (pintype "passive"))
      (node (ref "C5") (pin "2") (pinfunction "2_2") (pintype "passive"))
      (node (ref "C6") (pin "2") (pinfunction "2_2") (pintype "passive"))
      (node (ref "C7") (pin "2") (pinfunction "2_2") (pintype "passive"))
      (node (ref "C8") (pin "2") (pinfunction "2_2") (pintype "passive"))
      (node (ref "C9") (pin "2") (pinfunction "2_2") (pintype "passive"))
      (node (ref "CN1") (pin "5") (pinfunction "GND_5") (pintype "power_in"))
      (node (ref "CN1") (pin "GND1") (pinfunction "SHIELD_GND1") (pintype "bidirectional"))
      (node (ref "CN1") (pin "GND2") (pinfunction "SHIELD_GND2") (pintype "bidirectional"))
      (node (ref "CN2") (pin "4") (pinfunction "GND_4") (pintype "power_in"))
      (node (ref "CN2") (pin "P$2") (pinfunction "SHIELD_P$2") (pintype "bidirectional"))
      (node (ref "CN2") (pin "P$3") (pinfunction "SHIELD_P$3") (pintype "bidirectional"))
      (node (ref "CN2") (pin "P$4") (pinfunction "SHIELD_P$4") (pintype "bidirectional"))
      (node (ref "CN2") (pin "P$5") (pinfunction "SHIELD_P$5") (pintype "bidirectional"))
      (node (ref "CN3") (pin "4") (pinfunction "ID_4") (pintype "bidirectional"))
      (node (ref "CN3") (pin "5") (pinfunction "GND_5") (pintype "power_in"))
      (node (ref "CN3") (pin "GND1") (pinfunction "SHIELD_GND1") (pintype "bidirectional"))
      (node (ref "CN3") (pin "GND2") (pinfunction "SHIELD_GND2") (pintype "bidirectional"))
      (node (ref "CN3") (pin "GND3") (pinfunction "SHIELD_GND3") (pintype "bidirectional"))
      (node (ref "CN3") (pin "GND4") (pinfunction "SHIELD_GND4") (pintype "bidirectional"))
      (node (ref "CN4") (pin "P$1") (pinfunction "P$1_P$1") (pintype "bidirectional"))
      (node (ref "CN4") (pin "P$6") (pinfunction "P$6_P$6") (pintype "bidirectional"))
      (node (ref "CN6") (pin "5") (pinfunction "5_5") (pintype "bidirectional"))
      (node (ref "D1") (pin "2") (pinfunction "GND_2") (pintype "bidirectional"))
      (node (ref "IC1") (pin "27") (pinfunction "TSTPLL/48MCLK_27") (pintype "bidirectional"))
      (node (ref "IC1") (pin "28") (pinfunction "GND_28") (pintype "power_in"))
      (node (ref "IC1") (pin "31") (pinfunction "TSTMODE_31") (pintype "input"))
      (node (ref "IC1") (pin "6") (pinfunction "EEDATA/GANGED_6") (pintype "bidirectional"))
      (node (ref "IC1") (pin "7") (pinfunction "GND_7") (pintype "power_in"))
      (node (ref "IC1") (pin "8") (pinfunction "BUSPWR_8") (pintype "input"))
      (node (ref "IC1") (pin "EXP") (pinfunction "PAD_EXP") (pintype "power_in"))
      (node (ref "IC2") (pin "13") (pinfunction "GND_13") (pintype "power_in"))
      (node (ref "IC2") (pin "3") (pinfunction "GND_3") (pintype "power_in"))
      (node (ref "IC2") (pin "P$1") (pinfunction "GND_P$1") (pintype "power_in"))
      (node (ref "IC2") (pin "P$2") (pinfunction "GND_P$2") (pintype "power_in"))
      (node (ref "IC2") (pin "P$3") (pinfunction "GND_P$3") (pintype "power_in"))
      (node (ref "IC2") (pin "P$4") (pinfunction "GND_P$4") (pintype "power_in"))
      (node (ref "IC2") (pin "TAB") (pinfunction "GND_TAB") (pintype "power_in"))
      (node (ref "IC3") (pin "13") (pinfunction "GND_13") (pintype "power_in"))
      (node (ref "IC3") (pin "3") (pinfunction "GND_3") (pintype "power_in"))
      (node (ref "IC3") (pin "P$1") (pinfunction "GND_P$1") (pintype "power_in"))
      (node (ref "IC3") (pin "P$2") (pinfunction "GND_P$2") (pintype "power_in"))
      (node (ref "IC3") (pin "P$3") (pinfunction "GND_P$3") (pintype "power_in"))
      (node (ref "IC3") (pin "P$4") (pinfunction "GND_P$4") (pintype "power_in"))
      (node (ref "IC3") (pin "TAB") (pinfunction "GND_TAB") (pintype "power_in"))
      (node (ref "IC4") (pin "24") (pinfunction "VSS_24") (pintype "bidirectional"))
      (node (ref "IC4") (pin "5") (pinfunction "VSS_5") (pintype "bidirectional"))
      (node (ref "IC4") (pin "EXP") (pinfunction "VSS_EXP") (pintype "bidirectional"))
      (node (ref "IC4") (pin "P$1") (pinfunction "VSS_P$1") (pintype "bidirectional"))
      (node (ref "IC4") (pin "P$10") (pinfunction "VSS_P$10") (pintype "bidirectional"))
      (node (ref "IC4") (pin "P$2") (pinfunction "VSS_P$2") (pintype "bidirectional"))
      (node (ref "IC4") (pin "P$3") (pinfunction "VSS_P$3") (pintype "bidirectional"))
      (node (ref "IC4") (pin "P$4") (pinfunction "VSS_P$4") (pintype "bidirectional"))
      (node (ref "IC4") (pin "P$5") (pinfunction "VSS_P$5") (pintype "bidirectional"))
      (node (ref "IC4") (pin "P$6") (pinfunction "VSS_P$6") (pintype "bidirectional"))
      (node (ref "IC4") (pin "P$7") (pinfunction "VSS_P$7") (pintype "bidirectional"))
      (node (ref "IC4") (pin "P$9") (pinfunction "VSS_P$9") (pintype "bidirectional"))
      (node (ref "IC5") (pin "BOTTOM_LEFT") (pinfunction "GND_BOTTOM_LEFT") (pintype "bidirectional"))
      (node (ref "IC6") (pin "10") (pinfunction "GND_10") (pintype "bidirectional"))
      (node (ref "Q1") (pin "2") (pinfunction "S_2") (pintype "bidirectional"))
      (node (ref "Q2") (pin "2") (pinfunction "S_2") (pintype "bidirectional"))
      (node (ref "R17") (pin "1") (pinfunction "1_1") (pintype "passive"))
      (node (ref "R23") (pin "1") (pinfunction "1_1") (pintype "passive"))
      (node (ref "RN1") (pin "1") (pinfunction "1_1") (pintype "bidirectional"))
      (node (ref "RN1") (pin "2") (pinfunction "2_2") (pintype "bidirectional"))
      (node (ref "RN1") (pin "3") (pinfunction "3_3") (pintype "bidirectional"))
      (node (ref "RN1") (pin "4") (pinfunction "4_4") (pintype "bidirectional"))
      (node (ref "RN2") (pin "1") (pinfunction "1_1") (pintype "bidirectional"))
      (node (ref "RN2") (pin "2") (pinfunction "2_2") (pintype "bidirectional"))
      (node (ref "RN2") (pin "3") (pinfunction "3_3") (pintype "bidirectional"))
      (node (ref "RN2") (pin "4") (pinfunction "4_4") (pintype "bidirectional"))
      (node (ref "RN4") (pin "2A") (pinfunction "2A_2A") (pintype "bidirectional"))
      (node (ref "RN4") (pin "4A") (pinfunction "4A_4A") (pintype "bidirectional"))
      (node (ref "X1") (pin "GND") (pinfunction "CAN_GND") (pintype "bidirectional"))
    )
    (net (code "44") (name "KEY_X") (class "Default")
      (node (ref "C29") (pin "1") (pinfunction "1_1") (pintype "passive"))
      (node (ref "CN5") (pin "10") (pinfunction "10_10") (pintype "bidirectional"))
      (node (ref "R28") (pin "2") (pinfunction "2_2") (pintype "passive"))
    )
    (net (code "45") (name "Net-(CN1-D+)") (class "Default")
      (node (ref "CN1") (pin "3") (pinfunction "D+_3") (pintype "bidirectional"))
      (node (ref "R1") (pin "1") (pinfunction "1_1") (pintype "passive"))
    )
    (net (code "46") (name "Net-(CN1-D-)") (class "Default")
      (node (ref "CN1") (pin "2") (pinfunction "D-_2") (pintype "bidirectional"))
      (node (ref "R2") (pin "1") (pinfunction "1_1") (pintype "passive"))
    )
    (net (code "47") (name "Net-(CN1-VBUS)") (class "Default")
      (node (ref "CN1") (pin "1") (pinfunction "VBUS_1") (pintype "power_in"))
      (node (ref "D1") (pin "5") (pinfunction "V+_5") (pintype "bidirectional"))
    )
    (net (code "48") (name "Net-(CN3-D+)") (class "Default")
      (node (ref "CN3") (pin "3") (pinfunction "D+_3") (pintype "bidirectional"))
      (node (ref "R6") (pin "1") (pinfunction "1_1") (pintype "passive"))
      (node (ref "RN1") (pin "4A") (pinfunction "4A_4A") (pintype "bidirectional"))
    )
    (net (code "49") (name "Net-(CN3-D-)") (class "Default")
      (node (ref "CN3") (pin "2") (pinfunction "D-_2") (pintype "bidirectional"))
      (node (ref "R5") (pin "1") (pinfunction "1_1") (pintype "passive"))
      (node (ref "RN1") (pin "3A") (pinfunction "3A_3A") (pintype "bidirectional"))
    )
    (net (code "50") (name "Net-(IC1-DM1)") (class "Default")
      (node (ref "IC1") (pin "11") (pinfunction "DM1_11") (pintype "bidirectional"))
      (node (ref "R3") (pin "2") (pinfunction "2_2") (pintype "passive"))
    )
    (net (code "51") (name "Net-(IC1-DM2)") (class "Default")
      (node (ref "IC1") (pin "15") (pinfunction "DM2_15") (pintype "bidirectional"))
      (node (ref "R5") (pin "2") (pinfunction "2_2") (pintype "passive"))
    )
    (net (code "52") (name "Net-(IC1-DM3)") (class "Default")
      (node (ref "IC1") (pin "19") (pinfunction "DM3_19") (pintype "bidirectional"))
      (node (ref "R12") (pin "1") (pinfunction "1_1") (pintype "passive"))
    )
    (net (code "53") (name "Net-(IC1-DM4)") (class "Default")
      (node (ref "IC1") (pin "23") (pinfunction "DM4_23") (pintype "bidirectional"))
      (node (ref "R10") (pin "1") (pinfunction "1_1") (pintype "passive"))
    )
    (net (code "54") (name "Net-(IC1-DP1)") (class "Default")
      (node (ref "IC1") (pin "12") (pinfunction "DP1_12") (pintype "bidirectional"))
      (node (ref "R4") (pin "2") (pinfunction "2_2") (pintype "passive"))
    )
    (net (code "55") (name "Net-(IC1-DP2)") (class "Default")
      (node (ref "IC1") (pin "16") (pinfunction "DP2_16") (pintype "bidirectional"))
      (node (ref "R6") (pin "2") (pinfunction "2_2") (pintype "passive"))
    )
    (net (code "56") (name "Net-(IC1-DP3)") (class "Default")
      (node (ref "IC1") (pin "20") (pinfunction "DP3_20") (pintype "bidirectional"))
      (node (ref "R11") (pin "1") (pinfunction "1_1") (pintype "passive"))
    )
    (net (code "57") (name "Net-(IC1-DP4)") (class "Default")
      (node (ref "IC1") (pin "24") (pinfunction "DP4_24") (pintype "bidirectional"))
      (node (ref "R9") (pin "1") (pinfunction "1_1") (pintype "passive"))
    )
    (net (code "58") (name "Net-(IC1-XTAL1)") (class "Default")
      (node (ref "IC1") (pin "30") (pinfunction "XTAL1_30") (pintype "input"))
      (node (ref "X1") (pin "1") (pinfunction "XTAL1_1") (pintype "bidirectional"))
    )
    (net (code "59") (name "Net-(IC1-XTAL2)") (class "Default")
      (node (ref "IC1") (pin "29") (pinfunction "XTAL2_29") (pintype "output"))
      (node (ref "X1") (pin "2") (pinfunction "XTAL2_2") (pintype "bidirectional"))
    )
    (net (code "60") (name "Net-(IC1-~{RESET})") (class "Default")
      (node (ref "C8") (pin "1") (pinfunction "1_1") (pintype "passive"))
      (node (ref "IC1") (pin "4") (pinfunction "~{RESET}_4") (pintype "input"))
      (node (ref "R7") (pin "2") (pinfunction "2_2") (pintype "passive"))
    )
    (net (code "61") (name "Net-(IC4-VCAP)") (class "Default")
      (node (ref "C16") (pin "1") (pinfunction "1_1") (pintype "passive"))
      (node (ref "IC4") (pin "17") (pinfunction "VCAP_17") (pintype "bidirectional"))
    )
    (net (code "62") (name "Net-(IC6-C1+)") (class "Default")
      (node (ref "C41") (pin "2") (pinfunction "2_2") (pintype "passive"))
      (node (ref "IC6") (pin "9") (pinfunction "C1+_9") (pintype "bidirectional"))
    )
    (net (code "63") (name "Net-(IC6-C1-)") (class "Default")
      (node (ref "C41") (pin "1") (pinfunction "1_1") (pintype "passive"))
      (node (ref "IC6") (pin "2") (pinfunction "C1-_2") (pintype "bidirectional"))
    )
    (net (code "64") (name "Net-(IC6-RIN)") (class "Default")
      (node (ref "IC6") (pin "6") (pinfunction "RIN_6") (pintype "bidirectional"))
      (node (ref "L6") (pin "1") (pinfunction "1_1") (pintype "bidirectional"))
    )
    (net (code "65") (name "Net-(IC6-TOUT)") (class "Default")
      (node (ref "IC6") (pin "7") (pinfunction "TOUT_7") (pintype "bidirectional"))
      (node (ref "L5") (pin "1") (pinfunction "1_1") (pintype "bidirectional"))
    )
    (net (code "66") (name "Net-(IC6-V-)") (class "Default")
      (node (ref "C42") (pin "1") (pinfunction "1_1") (pintype "passive"))
      (node (ref "IC6") (pin "8") (pinfunction "V-_8") (pintype "bidirectional"))
    )
    (net (code "67") (name "Net-(IC6-VCC)") (class "Default")
      (node (ref "C40") (pin "1") (pinfunction "1_1") (pintype "passive"))
      (node (ref "IC6") (pin "1") (pinfunction "VCC_1") (pintype "bidirectional"))
      (node (ref "L4") (pin "2") (pinfunction "2_2") (pintype "bidirectional"))
    )
    (net (code "68") (name "Net-(Q1-D)") (class "Default")
      (node (ref "L2") (pin "1") (pinfunction "1_1") (pintype "bidirectional"))
      (node (ref "Q1") (pin "3") (pinfunction "D_3") (pintype "bidirectional"))
      (node (ref "RN4") (pin "3") (pinfunction "3_3") (pintype "bidirectional"))
    )
    (net (code "69") (name "Net-(Q2-G)") (class "Default")
      (node (ref "L3") (pin "1") (pinfunction "1_1") (pintype "bidirectional"))
      (node (ref "Q2") (pin "1") (pinfunction "G_1") (pintype "bidirectional"))
      (node (ref "RN4") (pin "2") (pinfunction "2_2") (pintype "bidirectional"))
    )
    (net (code "70") (name "PGC") (class "Default")
      (node (ref "IC4") (pin "19") (pinfunction "RB11_19") (pintype "bidirectional"))
    )
    (net (code "71") (name "PGD") (class "Default")
      (node (ref "IC4") (pin "18") (pinfunction "RB10_18") (pintype "bidirectional"))
    )
    (net (code "72") (name "PTT_X") (class "Default")
      (node (ref "C24") (pin "1") (pinfunction "1_1") (pintype "passive"))
      (node (ref "CN5") (pin "4") (pinfunction "4_4") (pintype "bidirectional"))
      (node (ref "R22") (pin "2") (pinfunction "2_2") (pintype "passive"))
    )
    (net (code "73") (name "PWR_X") (class "Default")
      (node (ref "C27") (pin "1") (pinfunction "1_1") (pintype "passive"))
      (node (ref "CN5") (pin "8") (pinfunction "8_8") (pintype "bidirectional"))
      (node (ref "R26") (pin "2") (pinfunction "2_2") (pintype "passive"))
    )
    (net (code "74") (name "UART_FROM_CAT") (class "Default")
      (node (ref "C9") (pin "1") (pinfunction "1_1") (pintype "passive"))
      (node (ref "IC2") (pin "2") (pinfunction "RXD_2") (pintype "input"))
      (node (ref "IC4") (pin "14") (pinfunction "RB8_14") (pintype "bidirectional"))
    )
    (net (code "75") (name "UART_FROM_K3") (class "Default")
      (node (ref "IC4") (pin "1") (pinfunction "RB0_1") (pintype "bidirectional"))
      (node (ref "Q2") (pin "3") (pinfunction "D_3") (pintype "bidirectional"))
      (node (ref "RN4") (pin "1") (pinfunction "1_1") (pintype "bidirectional"))
    )
    (net (code "76") (name "UART_FROM_P3") (class "Default")
      (node (ref "IC4") (pin "3") (pinfunction "RB2_3") (pintype "bidirectional"))
      (node (ref "IC6") (pin "5") (pinfunction "ROUT_5") (pintype "bidirectional"))
    )
    (net (code "77") (name "UART_FROM_WK") (class "Default")
      (node (ref "C11") (pin "1") (pinfunction "1_1") (pintype "passive"))
      (node (ref "IC3") (pin "2") (pinfunction "RXD_2") (pintype "input"))
      (node (ref "IC4") (pin "22") (pinfunction "RB14_22") (pintype "bidirectional"))
    )
    (net (code "78") (name "UART_TO_CAT") (class "Default")
      (node (ref "C12") (pin "1") (pinfunction "1_1") (pintype "passive"))
      (node (ref "IC2") (pin "15") (pinfunction "TXD_15") (pintype "output"))
      (node (ref "IC4") (pin "15") (pinfunction "RB9_15") (pintype "bidirectional"))
    )
    (net (code "79") (name "UART_TO_K3") (class "Default")
      (node (ref "IC4") (pin "2") (pinfunction "RB1_2") (pintype "bidirectional"))
      (node (ref "Q1") (pin "1") (pinfunction "G_1") (pintype "bidirectional"))
      (node (ref "RN4") (pin "4") (pinfunction "4_4") (pintype "bidirectional"))
    )
    (net (code "80") (name "UART_TO_P3") (class "Default")
      (node (ref "IC4") (pin "4") (pinfunction "RB3_4") (pintype "bidirectional"))
      (node (ref "IC6") (pin "4") (pinfunction "TIN_4") (pintype "bidirectional"))
    )
    (net (code "81") (name "UART_TO_WK") (class "Default")
      (node (ref "C10") (pin "1") (pinfunction "1_1") (pintype "passive"))
      (node (ref "IC3") (pin "15") (pinfunction "TXD_15") (pintype "output"))
      (node (ref "IC4") (pin "23") (pinfunction "RB15_23") (pintype "bidirectional"))
    )
    (net (code "82") (name "unconnected-(CN1-ID-Pad4)") (class "Default")
      (node (ref "CN1") (pin "4") (pinfunction "ID_4") (pintype "bidirectional"))
    )
    (net (code "83") (name "unconnected-(CN6-Pad2)") (class "Default")
      (node (ref "CN6") (pin "2") (pinfunction "2_2") (pintype "bidirectional"))
    )
    (net (code "84") (name "unconnected-(CN6-Pad4)") (class "Default")
      (node (ref "CN6") (pin "4") (pinfunction "4_4") (pintype "bidirectional"))
    )
    (net (code "85") (name "unconnected-(CN6-Pad6)") (class "Default")
      (node (ref "CN6") (pin "6") (pinfunction "6_6") (pintype "bidirectional"))
    )
    (net (code "86") (name "unconnected-(CN6-Pad7)") (class "Default")
      (node (ref "CN6") (pin "7") (pinfunction "7_7") (pintype "bidirectional"))
    )
    (net (code "87") (name "unconnected-(CN6-Pad8)") (class "Default")
      (node (ref "CN6") (pin "8") (pinfunction "8_8") (pintype "bidirectional"))
    )
    (net (code "88") (name "unconnected-(IC1-EECLK-Pad5)") (class "Default")
      (node (ref "IC1") (pin "5") (pinfunction "EECLK_5") (pintype "output"))
    )
    (net (code "89") (name "unconnected-(IC1-SUSPND-Pad32)") (class "Default")
      (node (ref "IC1") (pin "32") (pinfunction "SUSPND_32") (pintype "output"))
    )
    (net (code "90") (name "unconnected-(IC1-~{PWRON1}-Pad9)") (class "Default")
      (node (ref "IC1") (pin "9") (pinfunction "~{PWRON1}_9") (pintype "output"))
    )
    (net (code "91") (name "unconnected-(IC1-~{PWRON2}-Pad13)") (class "Default")
      (node (ref "IC1") (pin "13") (pinfunction "~{PWRON2}_13") (pintype "output"))
    )
    (net (code "92") (name "unconnected-(IC1-~{PWRON3}-Pad17)") (class "Default")
      (node (ref "IC1") (pin "17") (pinfunction "~{PWRON3}_17") (pintype "output"))
    )
    (net (code "93") (name "unconnected-(IC1-~{PWRON4}-Pad21)") (class "Default")
      (node (ref "IC1") (pin "21") (pinfunction "~{PWRON4}_21") (pintype "output"))
    )
    (net (code "94") (name "unconnected-(IC2-CBUS0-Pad12)") (class "Default")
      (node (ref "IC2") (pin "12") (pinfunction "CBUS0_12") (pintype "bidirectional"))
    )
    (net (code "95") (name "unconnected-(IC2-CBUS1-Pad11)") (class "Default")
      (node (ref "IC2") (pin "11") (pinfunction "CBUS1_11") (pintype "bidirectional"))
    )
    (net (code "96") (name "unconnected-(IC2-CBUS2-Pad5)") (class "Default")
      (node (ref "IC2") (pin "5") (pinfunction "CBUS2_5") (pintype "bidirectional"))
    )
    (net (code "97") (name "unconnected-(IC2-CBUS3-Pad14)") (class "Default")
      (node (ref "IC2") (pin "14") (pinfunction "CBUS3_14") (pintype "bidirectional"))
    )
    (net (code "98") (name "unconnected-(IC2-~{CTS}-Pad4)") (class "Default")
      (node (ref "IC2") (pin "4") (pinfunction "~{CTS}_4") (pintype "input"))
    )
    (net (code "99") (name "unconnected-(IC2-~{RTS}-Pad16)") (class "Default")
      (node (ref "IC2") (pin "16") (pinfunction "~{RTS}_16") (pintype "output"))
    )
    (net (code "100") (name "unconnected-(IC3-CBUS0-Pad12)") (class "Default")
      (node (ref "IC3") (pin "12") (pinfunction "CBUS0_12") (pintype "bidirectional"))
    )
    (net (code "101") (name "unconnected-(IC3-CBUS1-Pad11)") (class "Default")
      (node (ref "IC3") (pin "11") (pinfunction "CBUS1_11") (pintype "bidirectional"))
    )
    (net (code "102") (name "unconnected-(IC3-CBUS2-Pad5)") (class "Default")
      (node (ref "IC3") (pin "5") (pinfunction "CBUS2_5") (pintype "bidirectional"))
    )
    (net (code "103") (name "unconnected-(IC3-CBUS3-Pad14)") (class "Default")
      (node (ref "IC3") (pin "14") (pinfunction "CBUS3_14") (pintype "bidirectional"))
    )
    (net (code "104") (name "unconnected-(IC3-~{CTS}-Pad4)") (class "Default")
      (node (ref "IC3") (pin "4") (pinfunction "~{CTS}_4") (pintype "input"))
    )
    (net (code "105") (name "unconnected-(IC3-~{RTS}-Pad16)") (class "Default")
      (node (ref "IC3") (pin "16") (pinfunction "~{RTS}_16") (pintype "output"))
    )
    (net (code "106") (name "unconnected-(IC4-RA0-Pad27)") (class "Default")
      (node (ref "IC4") (pin "27") (pinfunction "RA0_27") (pintype "bidirectional"))
    )
    (net (code "107") (name "unconnected-(IC4-RA1-Pad28)") (class "Default")
      (node (ref "IC4") (pin "28") (pinfunction "RA1_28") (pintype "bidirectional"))
    )
    (net (code "108") (name "unconnected-(IC4-RA2-Pad6)") (class "Default")
      (node (ref "IC4") (pin "6") (pinfunction "RA2_6") (pintype "bidirectional"))
    )
    (net (code "109") (name "unconnected-(IC4-RA3-Pad7)") (class "Default")
      (node (ref "IC4") (pin "7") (pinfunction "RA3_7") (pintype "bidirectional"))
    )
    (net (code "110") (name "unconnected-(IC4-RA4-Pad9)") (class "Default")
      (node (ref "IC4") (pin "9") (pinfunction "RA4_9") (pintype "bidirectional"))
    )
    (net (code "111") (name "unconnected-(IC4-RB4-Pad8)") (class "Default")
      (node (ref "IC4") (pin "8") (pinfunction "RB4_8") (pintype "bidirectional"))
    )
    (net (code "112") (name "unconnected-(IC4-RB5-Pad11)") (class "Default")
      (node (ref "IC4") (pin "11") (pinfunction "RB5_11") (pintype "bidirectional"))
    )
    (net (code "113") (name "unconnected-(IC4-RB6-Pad12)") (class "Default")
      (node (ref "IC4") (pin "12") (pinfunction "RB6_12") (pintype "bidirectional"))
    )
    (net (code "114") (name "unconnected-(IC4-RB7-Pad13)") (class "Default")
      (node (ref "IC4") (pin "13") (pinfunction "RB7_13") (pintype "bidirectional"))
    )
    (net (code "115") (name "unconnected-(IC4-RB12-Pad20)") (class "Default")
      (node (ref "IC4") (pin "20") (pinfunction "RB12_20") (pintype "bidirectional"))
    )
    (net (code "116") (name "unconnected-(IC4-RB13-Pad21)") (class "Default")
      (node (ref "IC4") (pin "21") (pinfunction "RB13_21") (pintype "bidirectional"))
    )
    (net (code "117") (name "unconnected-(IC4-VBAT-Pad16)") (class "Default")
      (node (ref "IC4") (pin "16") (pinfunction "VBAT_16") (pintype "bidirectional"))
    )
    (net (code "118") (name "unconnected-(IC6-~{INVLD}-Pad3)") (class "Default")
      (node (ref "IC6") (pin "3") (pinfunction "~{INVLD}_3") (pintype "bidirectional"))
    )
    (net (code "119") (name "unconnected-(RN3-Pad4)") (class "Default")
      (node (ref "RN3") (pin "4") (pinfunction "4_4") (pintype "bidirectional"))
    )
    (net (code "120") (name "unconnected-(RN3-Pad4A)") (class "Default")
      (node (ref "RN3") (pin "4A") (pinfunction "4A_4A") (pintype "bidirectional"))
    )
    (net (code "121") (name "~{MCLR}") (class "Default")
      (node (ref "C17") (pin "1") (pinfunction "1_1") (pintype "passive"))
      (node (ref "IC4") (pin "26") (pinfunction "~{MCLR}_26") (pintype "bidirectional"))
      (node (ref "R15") (pin "1") (pinfunction "1_1") (pintype "passive"))
    )
  )
)
